# JETSON.net
KiCad netlist of a schematic drawn in Altium Designer
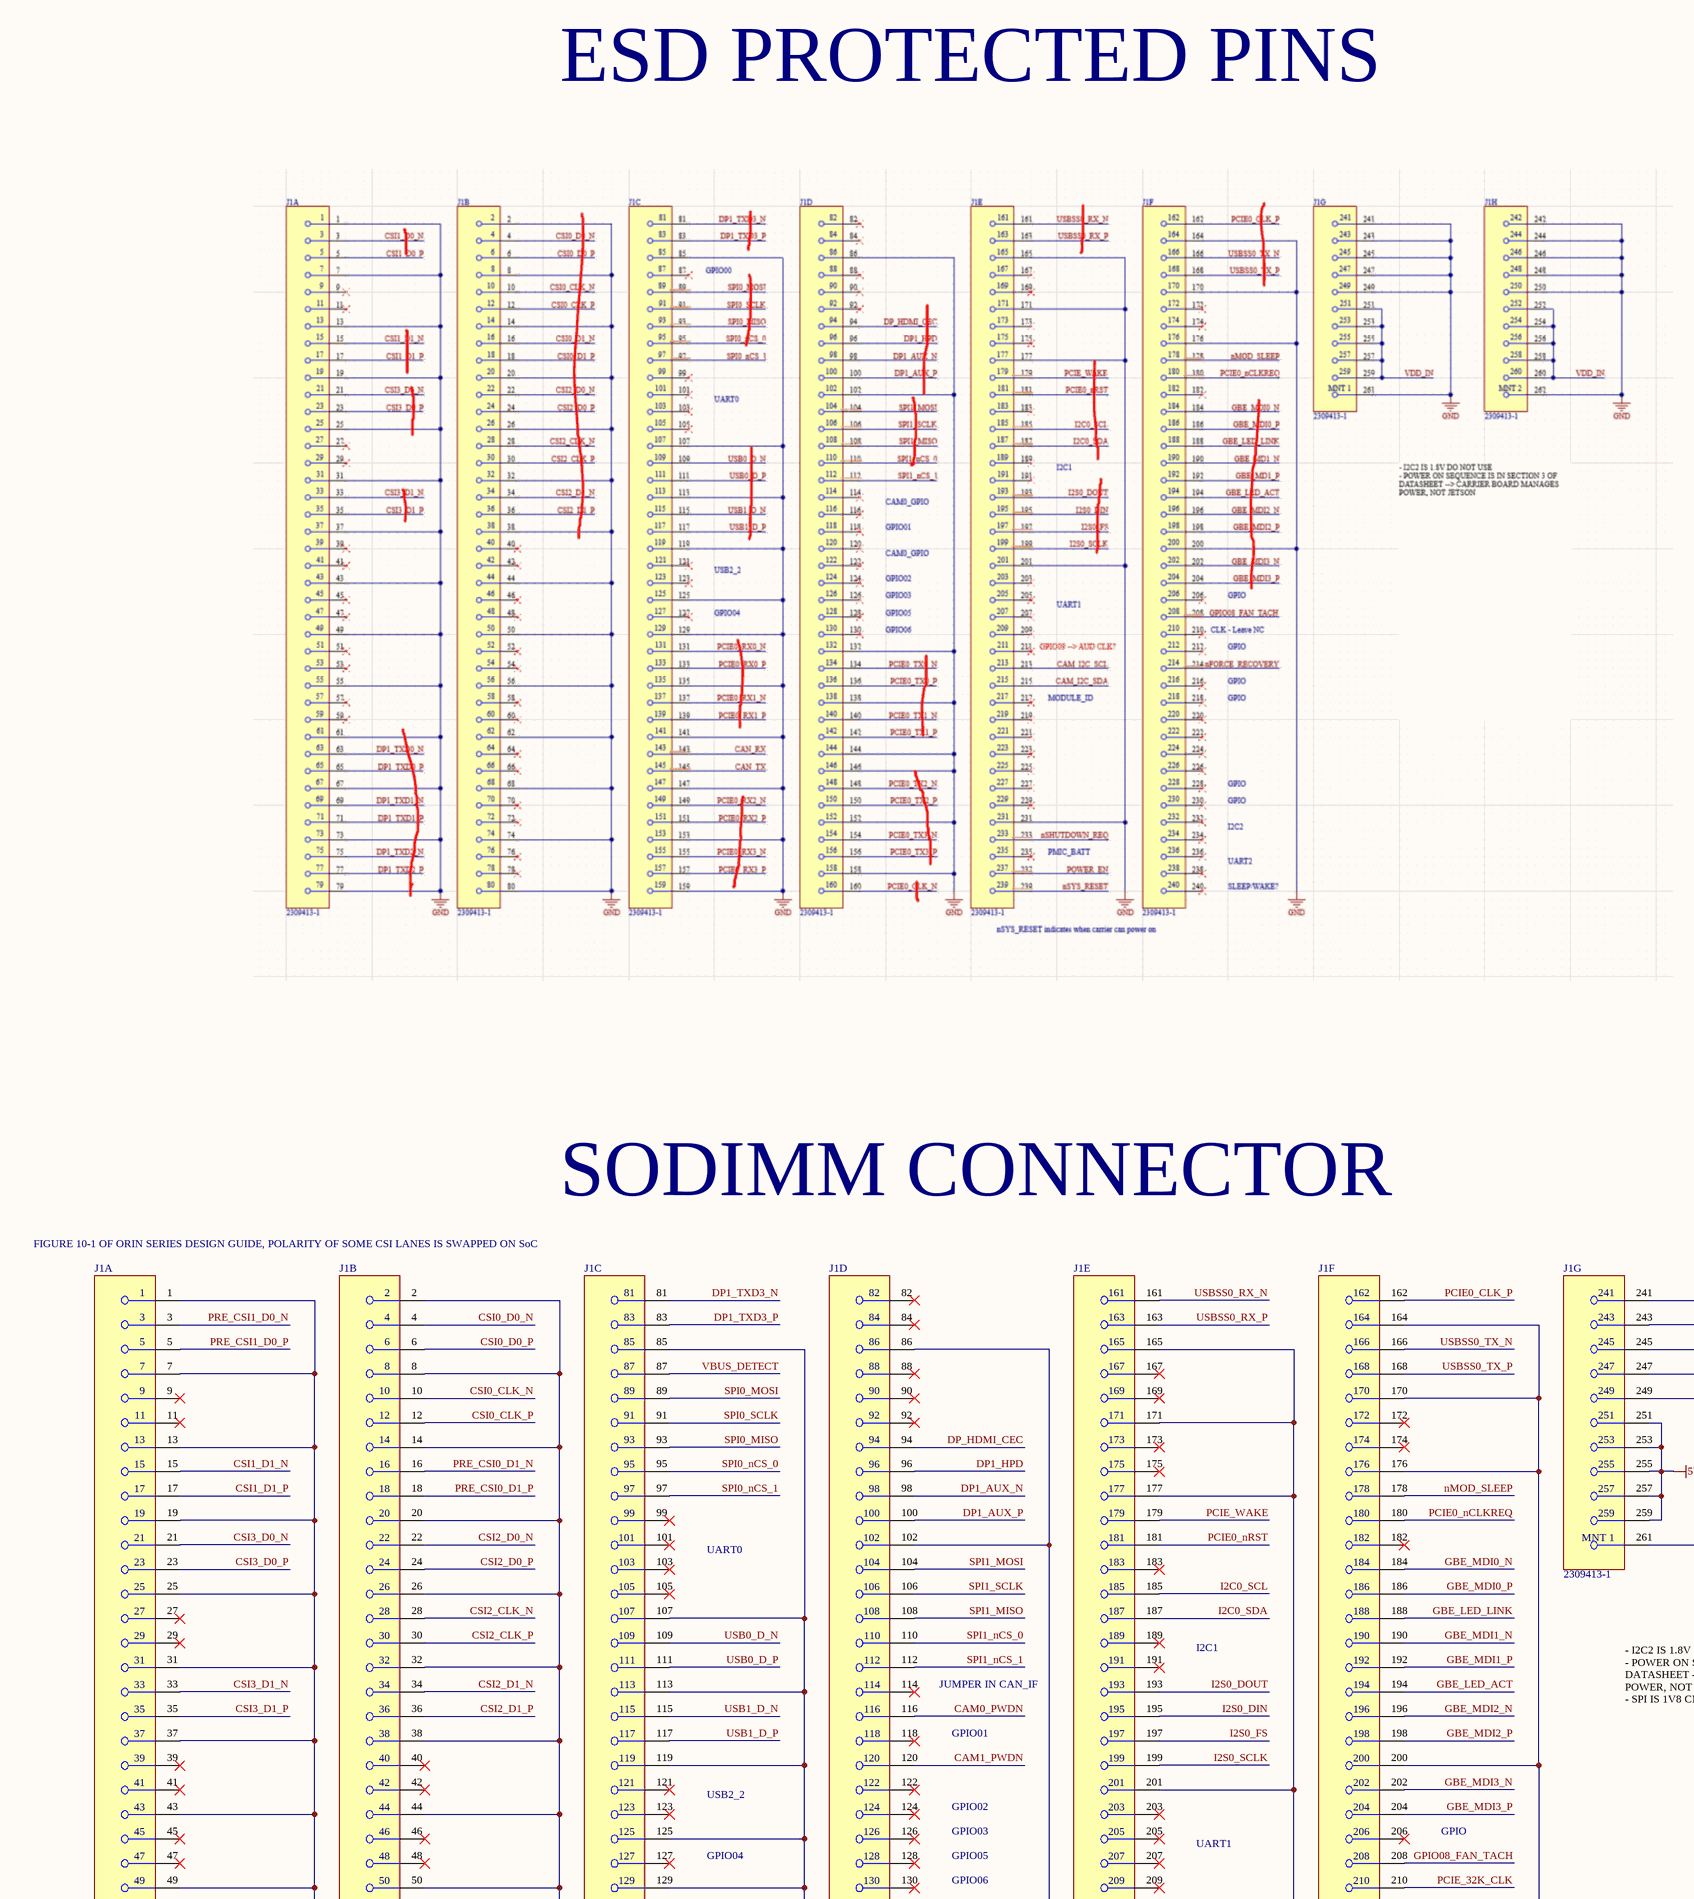
[diagram p0: JETSON.SchDoc, top left]
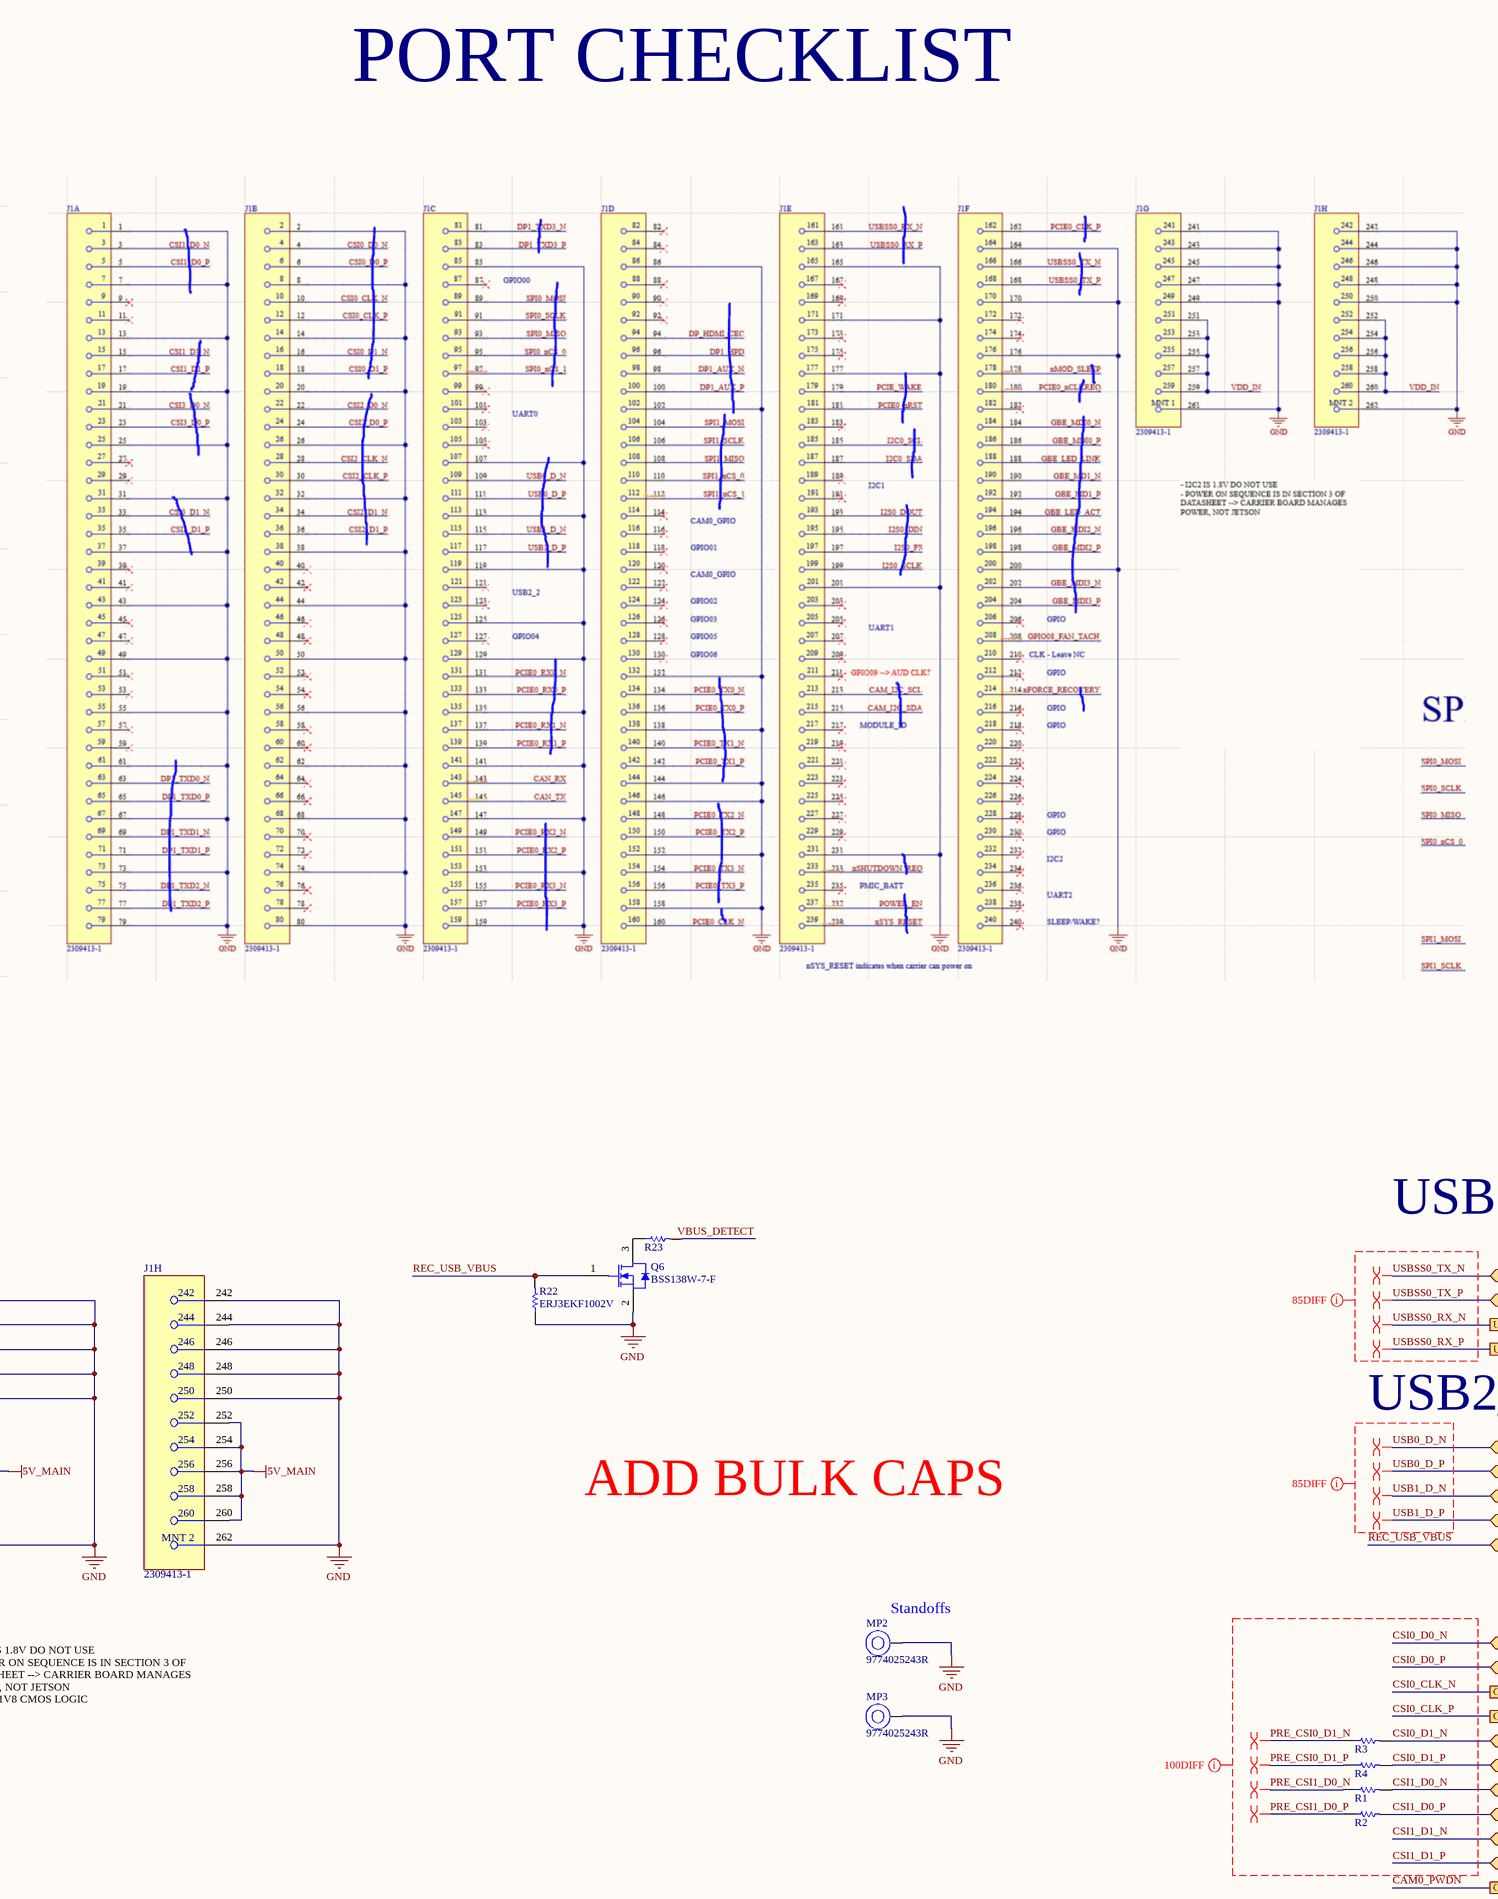
[diagram p1: JETSON.SchDoc, top middle]
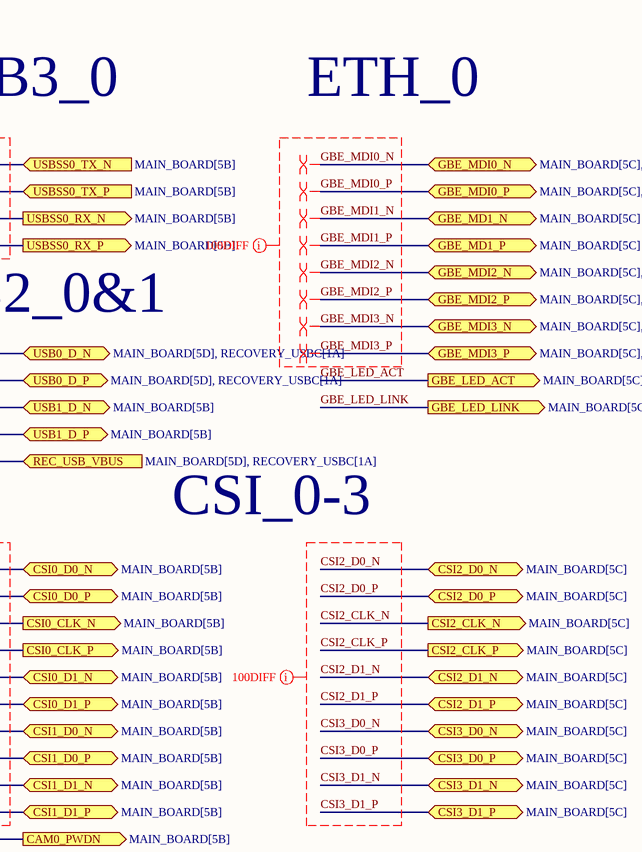
[diagram p2: JETSON.SchDoc, top right]
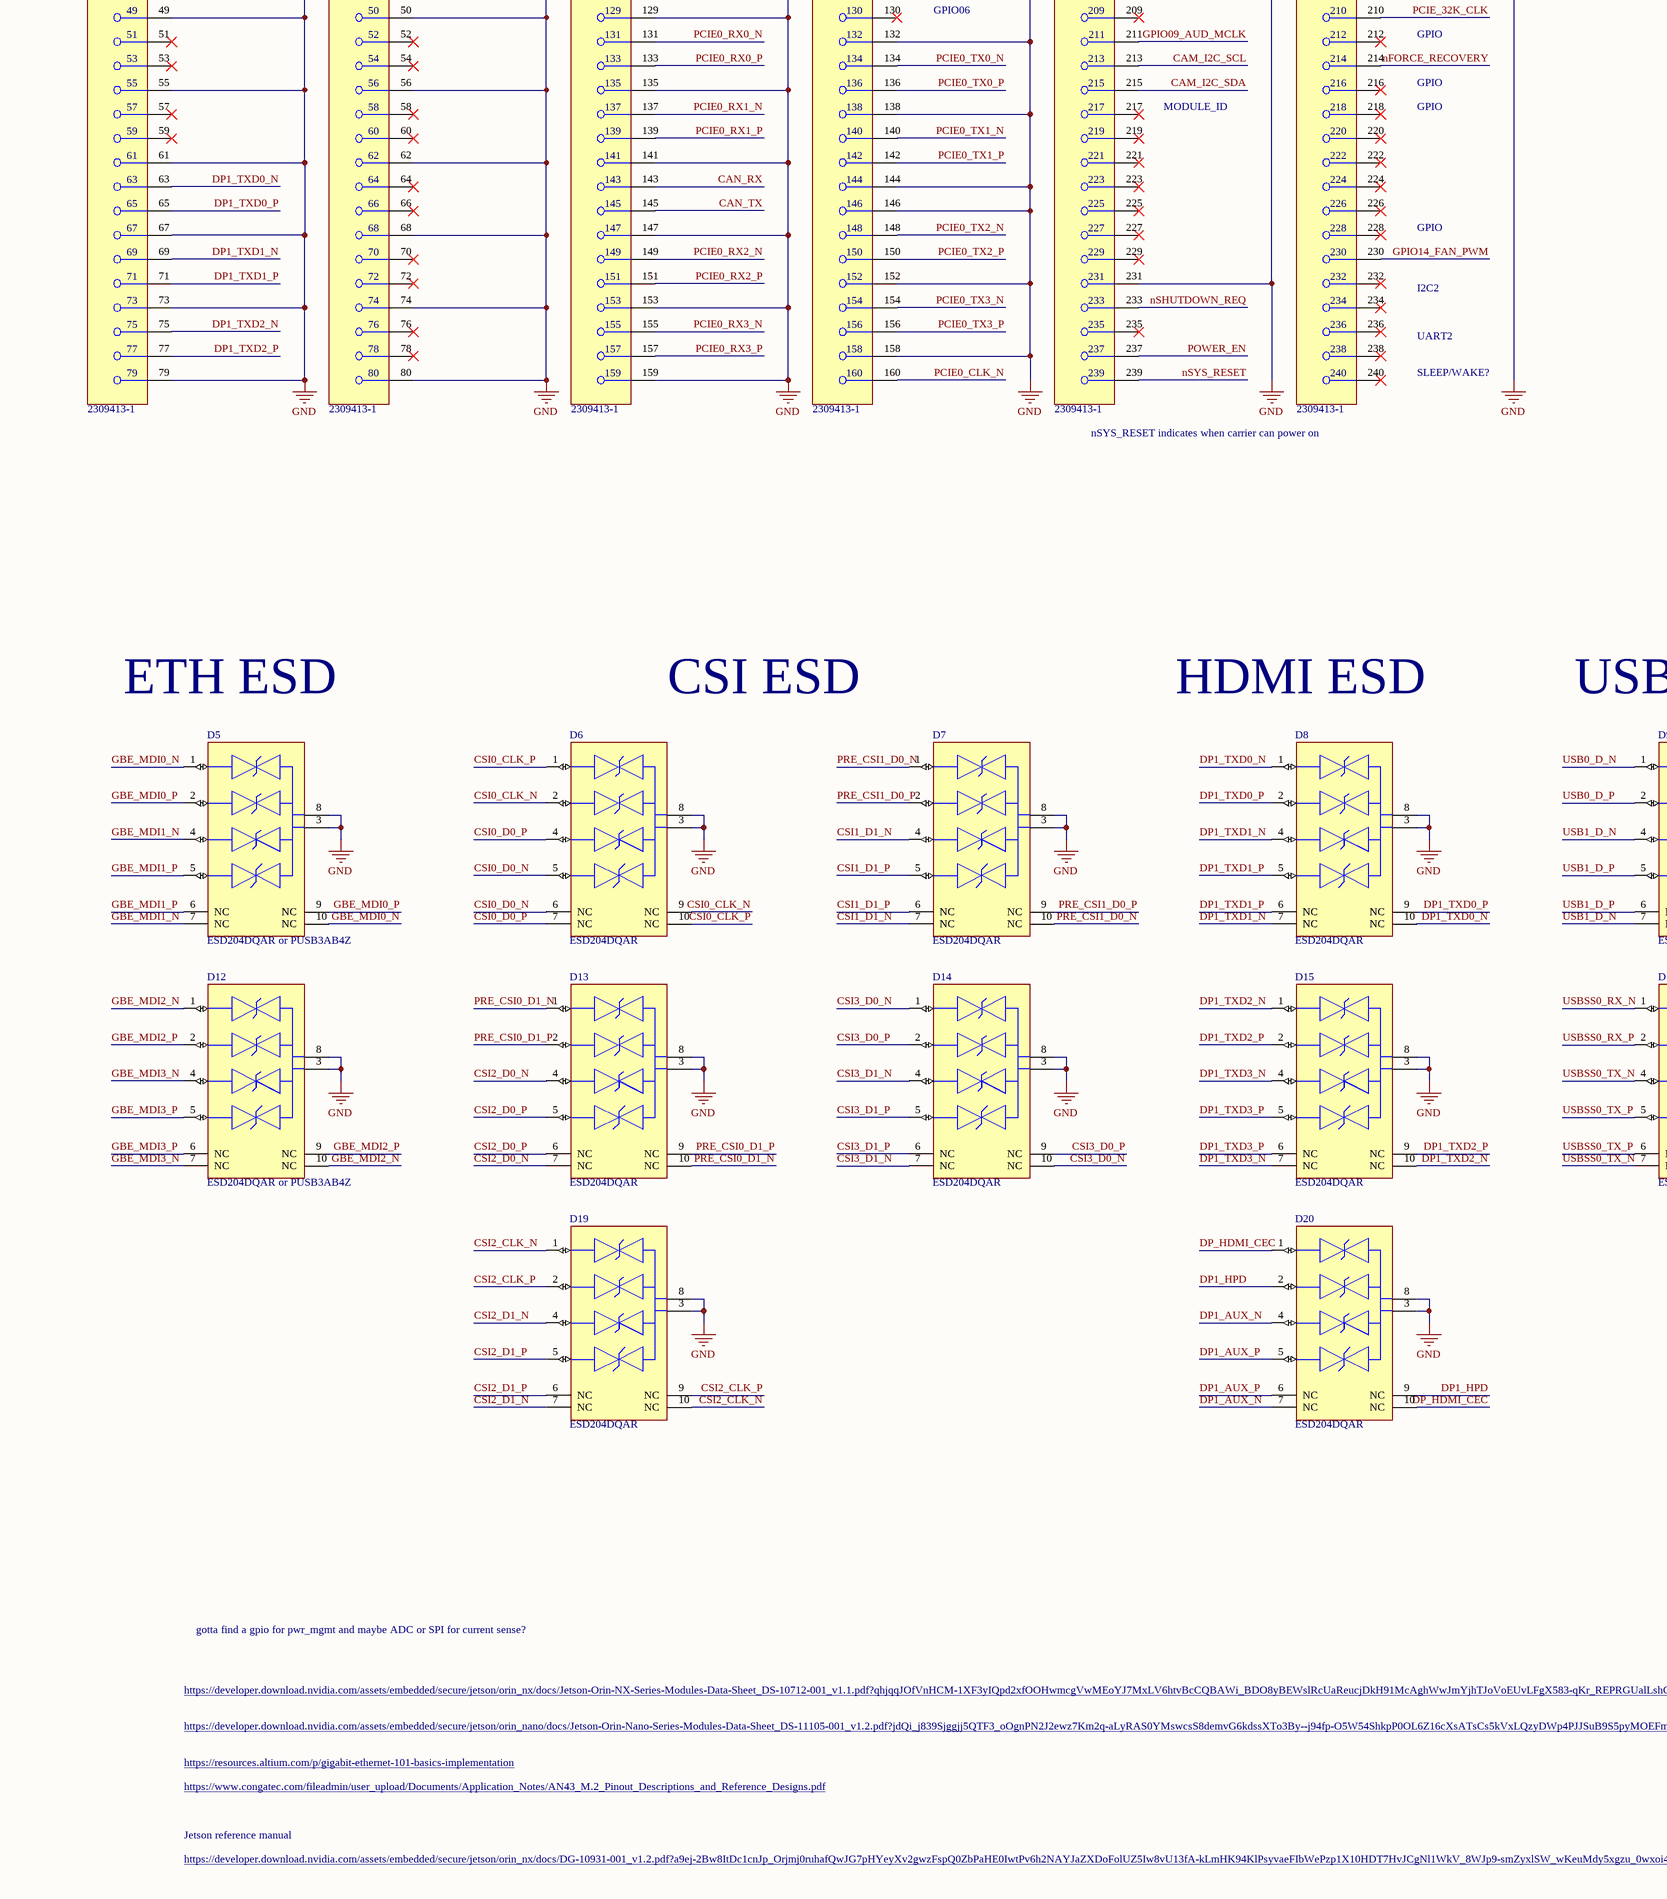
[diagram p3: JETSON.SchDoc, bottom left]
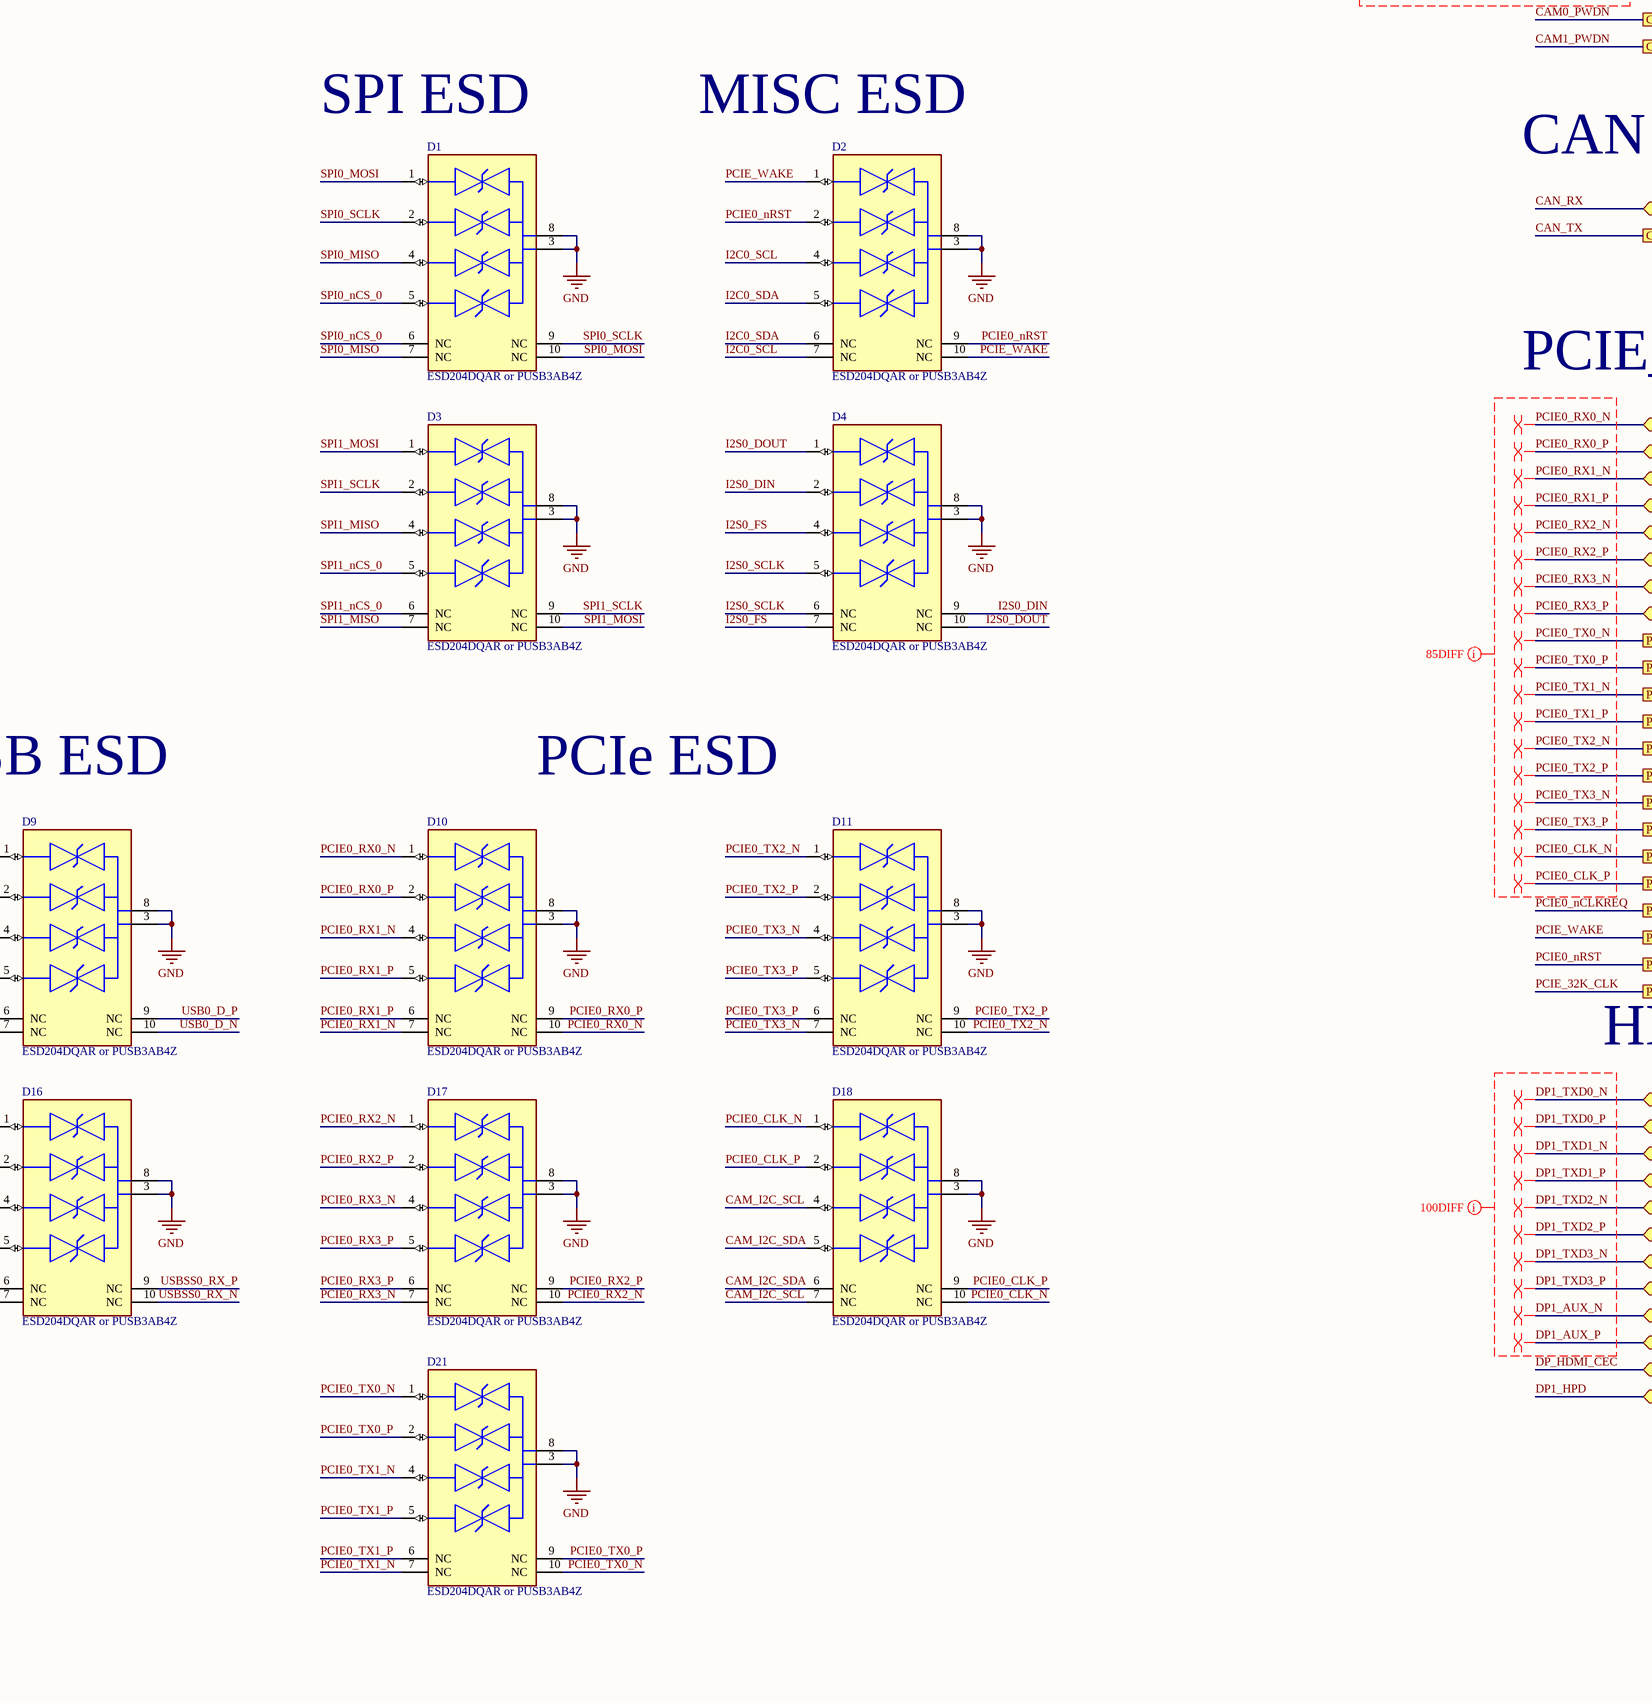
[diagram p4: JETSON.SchDoc, bottom middle]
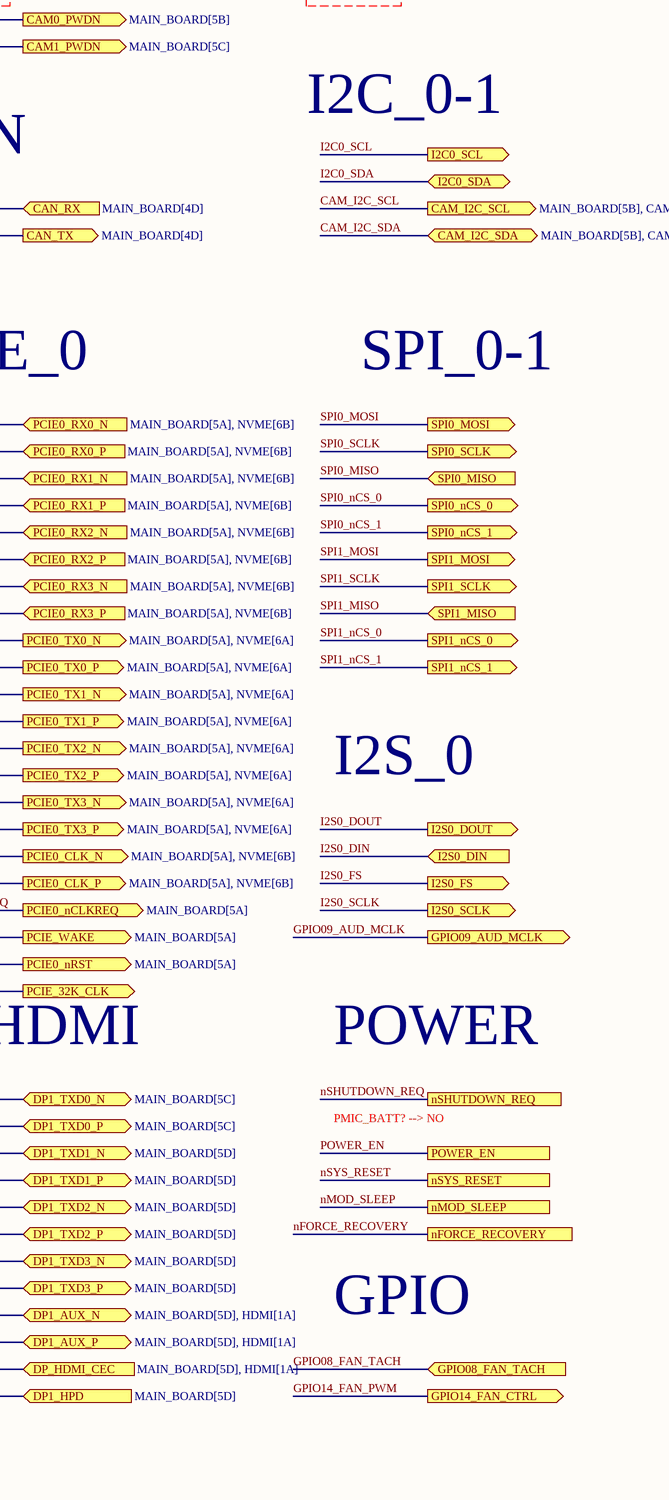
[diagram p5: JETSON.SchDoc, bottom right]

(export (version "E")
  (design (tool "Eeschema 10.0.6"))
  (components
    (comp (ref "D1")
      (value "ESD204DQAR or PUSB3AB4Z")
      (footprint "FP-DQA0010A-MFG")
      (description "4-CHANNEL LOW-CAPACITANCE SURGE")
      (fields
        (field (name "MANUFACTURER") "Texas Instruments")
        (field (name "OCTOPART") "https://octopart.com/esd204dqar-texas+instruments-89917476")
      )
      (libsource (lib "Altium Content Vault") (part "1465e58c1818c7767b55926832f0bf5"))
    )
    (comp (ref "D2")
      (value "ESD204DQAR or PUSB3AB4Z")
      (footprint "FP-DQA0010A-MFG")
      (description "4-CHANNEL LOW-CAPACITANCE SURGE")
      (fields
        (field (name "MANUFACTURER") "Texas Instruments")
        (field (name "OCTOPART") "https://octopart.com/esd204dqar-texas+instruments-89917476")
      )
      (libsource (lib "Altium Content Vault") (part "1465e58c1818c7767b55926832f0bf5"))
    )
    (comp (ref "D3")
      (value "ESD204DQAR or PUSB3AB4Z")
      (footprint "FP-DQA0010A-MFG")
      (description "4-CHANNEL LOW-CAPACITANCE SURGE")
      (fields
        (field (name "MANUFACTURER") "Texas Instruments")
        (field (name "OCTOPART") "https://octopart.com/esd204dqar-texas+instruments-89917476")
      )
      (libsource (lib "Altium Content Vault") (part "1465e58c1818c7767b55926832f0bf5"))
    )
    (comp (ref "D4")
      (value "ESD204DQAR or PUSB3AB4Z")
      (footprint "FP-DQA0010A-MFG")
      (description "4-CHANNEL LOW-CAPACITANCE SURGE")
      (fields
        (field (name "MANUFACTURER") "Texas Instruments")
        (field (name "OCTOPART") "https://octopart.com/esd204dqar-texas+instruments-89917476")
      )
      (libsource (lib "Altium Content Vault") (part "1465e58c1818c7767b55926832f0bf5"))
    )
    (comp (ref "D5")
      (value "ESD204DQAR or PUSB3AB4Z")
      (footprint "FP-DQA0010A-MFG")
      (description "4-CHANNEL LOW-CAPACITANCE SURGE")
      (fields
        (field (name "MANUFACTURER") "Texas Instruments")
        (field (name "OCTOPART") "https://octopart.com/esd204dqar-texas+instruments-89917476")
      )
      (libsource (lib "Altium Content Vault") (part "1465e58c1818c7767b55926832f0bf5"))
    )
    (comp (ref "D6")
      (value "ESD204DQAR")
      (footprint "FP-DQA0010A-MFG")
      (description "4-CHANNEL LOW-CAPACITANCE SURGE")
      (fields
        (field (name "MANUFACTURER") "Texas Instruments")
        (field (name "OCTOPART") "https://octopart.com/esd204dqar-texas+instruments-89917476")
      )
      (libsource (lib "Altium Content Vault") (part "1465e58c1818c7767b55926832f0bf5"))
    )
    (comp (ref "D7")
      (value "ESD204DQAR")
      (footprint "FP-DQA0010A-MFG")
      (description "4-CHANNEL LOW-CAPACITANCE SURGE")
      (fields
        (field (name "MANUFACTURER") "Texas Instruments")
        (field (name "OCTOPART") "https://octopart.com/esd204dqar-texas+instruments-89917476")
      )
      (libsource (lib "Altium Content Vault") (part "1465e58c1818c7767b55926832f0bf5"))
    )
    (comp (ref "D8")
      (value "ESD204DQAR")
      (footprint "FP-DQA0010A-MFG")
      (description "4-CHANNEL LOW-CAPACITANCE SURGE")
      (fields
        (field (name "MANUFACTURER") "Texas Instruments")
        (field (name "OCTOPART") "https://octopart.com/esd204dqar-texas+instruments-89917476")
      )
      (libsource (lib "Altium Content Vault") (part "1465e58c1818c7767b55926832f0bf5"))
    )
    (comp (ref "D9")
      (value "ESD204DQAR or PUSB3AB4Z")
      (footprint "FP-DQA0010A-MFG")
      (description "4-CHANNEL LOW-CAPACITANCE SURGE")
      (fields
        (field (name "MANUFACTURER") "Texas Instruments")
        (field (name "OCTOPART") "https://octopart.com/esd204dqar-texas+instruments-89917476")
      )
      (libsource (lib "Altium Content Vault") (part "1465e58c1818c7767b55926832f0bf5"))
    )
    (comp (ref "D10")
      (value "ESD204DQAR or PUSB3AB4Z")
      (footprint "FP-DQA0010A-MFG")
      (description "4-CHANNEL LOW-CAPACITANCE SURGE")
      (fields
        (field (name "MANUFACTURER") "Texas Instruments")
        (field (name "OCTOPART") "https://octopart.com/esd204dqar-texas+instruments-89917476")
      )
      (libsource (lib "Altium Content Vault") (part "1465e58c1818c7767b55926832f0bf5"))
    )
    (comp (ref "D11")
      (value "ESD204DQAR or PUSB3AB4Z")
      (footprint "FP-DQA0010A-MFG")
      (description "4-CHANNEL LOW-CAPACITANCE SURGE")
      (fields
        (field (name "MANUFACTURER") "Texas Instruments")
        (field (name "OCTOPART") "https://octopart.com/esd204dqar-texas+instruments-89917476")
      )
      (libsource (lib "Altium Content Vault") (part "1465e58c1818c7767b55926832f0bf5"))
    )
    (comp (ref "D12")
      (value "ESD204DQAR or PUSB3AB4Z")
      (footprint "FP-DQA0010A-MFG")
      (description "4-CHANNEL LOW-CAPACITANCE SURGE")
      (fields
        (field (name "MANUFACTURER") "Texas Instruments")
        (field (name "OCTOPART") "https://octopart.com/esd204dqar-texas+instruments-89917476")
      )
      (libsource (lib "Altium Content Vault") (part "1465e58c1818c7767b55926832f0bf5"))
    )
    (comp (ref "D13")
      (value "ESD204DQAR")
      (footprint "FP-DQA0010A-MFG")
      (description "4-CHANNEL LOW-CAPACITANCE SURGE")
      (fields
        (field (name "MANUFACTURER") "Texas Instruments")
        (field (name "OCTOPART") "https://octopart.com/esd204dqar-texas+instruments-89917476")
      )
      (libsource (lib "Altium Content Vault") (part "1465e58c1818c7767b55926832f0bf5"))
    )
    (comp (ref "D14")
      (value "ESD204DQAR")
      (footprint "FP-DQA0010A-MFG")
      (description "4-CHANNEL LOW-CAPACITANCE SURGE")
      (fields
        (field (name "MANUFACTURER") "Texas Instruments")
        (field (name "OCTOPART") "https://octopart.com/esd204dqar-texas+instruments-89917476")
      )
      (libsource (lib "Altium Content Vault") (part "1465e58c1818c7767b55926832f0bf5"))
    )
    (comp (ref "D15")
      (value "ESD204DQAR")
      (footprint "FP-DQA0010A-MFG")
      (description "4-CHANNEL LOW-CAPACITANCE SURGE")
      (fields
        (field (name "MANUFACTURER") "Texas Instruments")
        (field (name "OCTOPART") "https://octopart.com/esd204dqar-texas+instruments-89917476")
      )
      (libsource (lib "Altium Content Vault") (part "1465e58c1818c7767b55926832f0bf5"))
    )
    (comp (ref "D16")
      (value "ESD204DQAR or PUSB3AB4Z")
      (footprint "FP-DQA0010A-MFG")
      (description "4-CHANNEL LOW-CAPACITANCE SURGE")
      (fields
        (field (name "MANUFACTURER") "Texas Instruments")
        (field (name "OCTOPART") "https://octopart.com/esd204dqar-texas+instruments-89917476")
      )
      (libsource (lib "Altium Content Vault") (part "1465e58c1818c7767b55926832f0bf5"))
    )
    (comp (ref "D17")
      (value "ESD204DQAR or PUSB3AB4Z")
      (footprint "FP-DQA0010A-MFG")
      (description "4-CHANNEL LOW-CAPACITANCE SURGE")
      (fields
        (field (name "MANUFACTURER") "Texas Instruments")
        (field (name "OCTOPART") "https://octopart.com/esd204dqar-texas+instruments-89917476")
      )
      (libsource (lib "Altium Content Vault") (part "1465e58c1818c7767b55926832f0bf5"))
    )
    (comp (ref "D18")
      (value "ESD204DQAR or PUSB3AB4Z")
      (footprint "FP-DQA0010A-MFG")
      (description "4-CHANNEL LOW-CAPACITANCE SURGE")
      (fields
        (field (name "MANUFACTURER") "Texas Instruments")
        (field (name "OCTOPART") "https://octopart.com/esd204dqar-texas+instruments-89917476")
      )
      (libsource (lib "Altium Content Vault") (part "1465e58c1818c7767b55926832f0bf5"))
    )
    (comp (ref "D19")
      (value "ESD204DQAR")
      (footprint "FP-DQA0010A-MFG")
      (description "4-CHANNEL LOW-CAPACITANCE SURGE")
      (fields
        (field (name "MANUFACTURER") "Texas Instruments")
        (field (name "OCTOPART") "https://octopart.com/esd204dqar-texas+instruments-89917476")
      )
      (libsource (lib "Altium Content Vault") (part "1465e58c1818c7767b55926832f0bf5"))
    )
    (comp (ref "D20")
      (value "ESD204DQAR")
      (footprint "FP-DQA0010A-MFG")
      (description "4-CHANNEL LOW-CAPACITANCE SURGE")
      (fields
        (field (name "MANUFACTURER") "Texas Instruments")
        (field (name "OCTOPART") "https://octopart.com/esd204dqar-texas+instruments-89917476")
      )
      (libsource (lib "Altium Content Vault") (part "1465e58c1818c7767b55926832f0bf5"))
    )
    (comp (ref "D21")
      (value "ESD204DQAR or PUSB3AB4Z")
      (footprint "FP-DQA0010A-MFG")
      (description "4-CHANNEL LOW-CAPACITANCE SURGE")
      (fields
        (field (name "MANUFACTURER") "Texas Instruments")
        (field (name "OCTOPART") "https://octopart.com/esd204dqar-texas+instruments-89917476")
      )
      (libsource (lib "Altium Content Vault") (part "1465e58c1818c7767b55926832f0bf5"))
    )
    (comp (ref "J1")
      (value "2309413-1")
      (footprint "FP-2309413-1-MFG")
      (description "DDR4 SODIMM 260P 9.2H STD")
      (fields
        (field (name "OCTOPART") "https://octopart.com/2309413-1-te+connectivity-84799194")
        (field (name "MANUFACTURER") "TE Connectivity")
      )
      (libsource (lib "Altium Content Vault") (part "4d1075b24ee2591bdcd47d674b3d2aa"))
    )
    (comp (ref "MP2")
      (value "9774025243R")
      (footprint "9774025243")
      (description "9774025243R Spacer Material: Steel, Tin-Plated Mounting: SMT Series: WA-SMST Thread D: M2")
      (libsource (lib "Altium Content Vault") (part "Spacer"))
    )
    (comp (ref "MP3")
      (value "9774025243R")
      (footprint "9774025243")
      (description "9774025243R Spacer Material: Steel, Tin-Plated Mounting: SMT Series: WA-SMST Thread D: M2")
      (libsource (lib "Altium Content Vault") (part "Spacer"))
    )
    (comp (ref "Q6")
      (value "BSS138W-7-F")
      (footprint "DIOD-SOT323-3_V")
      (fields (field (name "MANUFACTURER") "DiodesIncorporated"))
      (libsource (lib "Altium Content Vault") (part "NEMOS-GSD-3"))
    )
    (comp (ref "R1")
      (value "0402 JUMPER 0 OHM")
      (footprint "RESC1005X40X25NL05T05")
      (description "READ THE NAME")
      (libsource (lib "uORocketry Hardware") (part "RES"))
    )
    (comp (ref "R2")
      (value "0402 JUMPER 0 OHM")
      (footprint "RESC1005X40X25NL05T05")
      (description "READ THE NAME")
      (libsource (lib "uORocketry Hardware") (part "RES"))
    )
    (comp (ref "R3")
      (value "0402 JUMPER 0 OHM")
      (footprint "RESC1005X40X25NL05T05")
      (description "READ THE NAME")
      (libsource (lib "uORocketry Hardware") (part "RES"))
    )
    (comp (ref "R4")
      (value "0402 JUMPER 0 OHM")
      (footprint "RESC1005X40X25NL05T05")
      (description "READ THE NAME")
      (libsource (lib "uORocketry Hardware") (part "RES"))
    )
    (comp (ref "R22")
      (value "ERJ3EKF1002V")
      (footprint "RESC1609X55X30LL15T15")
      (description "Chip Resistor, 10 KOhm, +/- 1%, 0.1 W, -55 to 155 degC, 0603 (1608 Metric), RoHS, Tape and Reel")
      (fields (field (name "TOLERANCE") "1%") (field (name "MANUFACTURER") "Panasonic"))
      (libsource (lib "Altium Content Vault") (part "RES-2"))
    )
    (comp (ref "R23")
      (value "0402 JUMPER 0 OHM")
      (footprint "RESC1005X40X25NL05T05")
      (description "READ THE NAME")
      (libsource (lib "uORocketry Hardware") (part "RES"))
    )
  )
  (nets
    (net (code "1") (name "/CAM0_PWDN") (class "Default")
      (node (ref "J1") (pin "116") (pinfunction "116_116") (pintype "passive"))
    )
    (net (code "2") (name "/CAM1_PWDN") (class "Default")
      (node (ref "J1") (pin "120") (pinfunction "120_120") (pintype "passive"))
    )
    (net (code "3") (name "/CAM_I2C_SCL") (class "Default")
      (node (ref "D18") (pin "4") (pinfunction "IO3_4") (pintype "bidirectional"))
      (node (ref "D18") (pin "7") (pinfunction "NC_7") (pintype "passive"))
      (node (ref "J1") (pin "213") (pinfunction "213_213") (pintype "passive"))
    )
    (net (code "4") (name "/CAM_I2C_SDA") (class "Default")
      (node (ref "D18") (pin "5") (pinfunction "IO4_5") (pintype "bidirectional"))
      (node (ref "D18") (pin "6") (pinfunction "NC_6") (pintype "passive"))
      (node (ref "J1") (pin "215") (pinfunction "215_215") (pintype "passive"))
    )
    (net (code "5") (name "/CAN_RX") (class "Default")
      (node (ref "J1") (pin "143") (pinfunction "143_143") (pintype "passive"))
    )
    (net (code "6") (name "/CAN_TX") (class "Default")
      (node (ref "J1") (pin "145") (pinfunction "145_145") (pintype "passive"))
    )
    (net (code "7") (name "/CSI0_CLK_N") (class "Default")
      (node (ref "D6") (pin "2") (pinfunction "IO2_2") (pintype "bidirectional"))
      (node (ref "D6") (pin "9") (pinfunction "NC_9") (pintype "passive"))
      (node (ref "J1") (pin "10") (pinfunction "10_10") (pintype "passive"))
    )
    (net (code "8") (name "/CSI0_CLK_P") (class "Default")
      (node (ref "D6") (pin "1") (pinfunction "IO1_1") (pintype "bidirectional"))
      (node (ref "D6") (pin "10") (pinfunction "NC_10") (pintype "passive"))
      (node (ref "J1") (pin "12") (pinfunction "12_12") (pintype "passive"))
    )
    (net (code "9") (name "/CSI0_D0_N") (class "Default")
      (node (ref "D6") (pin "5") (pinfunction "IO4_5") (pintype "bidirectional"))
      (node (ref "D6") (pin "6") (pinfunction "NC_6") (pintype "passive"))
      (node (ref "J1") (pin "4") (pinfunction "4_4") (pintype "passive"))
    )
    (net (code "10") (name "/CSI0_D0_P") (class "Default")
      (node (ref "D6") (pin "4") (pinfunction "IO3_4") (pintype "bidirectional"))
      (node (ref "D6") (pin "7") (pinfunction "NC_7") (pintype "passive"))
      (node (ref "J1") (pin "6") (pinfunction "6_6") (pintype "passive"))
    )
    (net (code "11") (name "/CSI0_D1_N") (class "Default")
      (node (ref "R3") (pin "2") (pinfunction "2_2") (pintype "passive"))
    )
    (net (code "12") (name "/CSI0_D1_P") (class "Default")
      (node (ref "R4") (pin "2") (pinfunction "2_2") (pintype "passive"))
    )
    (net (code "13") (name "/CSI1_D0_N") (class "Default")
      (node (ref "R1") (pin "2") (pinfunction "2_2") (pintype "passive"))
    )
    (net (code "14") (name "/CSI1_D0_P") (class "Default")
      (node (ref "R2") (pin "2") (pinfunction "2_2") (pintype "passive"))
    )
    (net (code "15") (name "/CSI1_D1_N") (class "Default")
      (node (ref "D7") (pin "4") (pinfunction "IO3_4") (pintype "bidirectional"))
      (node (ref "D7") (pin "7") (pinfunction "NC_7") (pintype "passive"))
      (node (ref "J1") (pin "15") (pinfunction "15_15") (pintype "passive"))
    )
    (net (code "16") (name "/CSI1_D1_P") (class "Default")
      (node (ref "D7") (pin "5") (pinfunction "IO4_5") (pintype "bidirectional"))
      (node (ref "D7") (pin "6") (pinfunction "NC_6") (pintype "passive"))
      (node (ref "J1") (pin "17") (pinfunction "17_17") (pintype "passive"))
    )
    (net (code "17") (name "/CSI2_CLK_N") (class "Default")
      (node (ref "D19") (pin "1") (pinfunction "IO1_1") (pintype "bidirectional"))
      (node (ref "D19") (pin "10") (pinfunction "NC_10") (pintype "passive"))
      (node (ref "J1") (pin "28") (pinfunction "28_28") (pintype "passive"))
    )
    (net (code "18") (name "/CSI2_CLK_P") (class "Default")
      (node (ref "D19") (pin "2") (pinfunction "IO2_2") (pintype "bidirectional"))
      (node (ref "D19") (pin "9") (pinfunction "NC_9") (pintype "passive"))
      (node (ref "J1") (pin "30") (pinfunction "30_30") (pintype "passive"))
    )
    (net (code "19") (name "/CSI2_D0_N") (class "Default")
      (node (ref "D13") (pin "4") (pinfunction "IO3_4") (pintype "bidirectional"))
      (node (ref "D13") (pin "7") (pinfunction "NC_7") (pintype "passive"))
      (node (ref "J1") (pin "22") (pinfunction "22_22") (pintype "passive"))
    )
    (net (code "20") (name "/CSI2_D0_P") (class "Default")
      (node (ref "D13") (pin "5") (pinfunction "IO4_5") (pintype "bidirectional"))
      (node (ref "D13") (pin "6") (pinfunction "NC_6") (pintype "passive"))
      (node (ref "J1") (pin "24") (pinfunction "24_24") (pintype "passive"))
    )
    (net (code "21") (name "/CSI2_D1_N") (class "Default")
      (node (ref "D19") (pin "4") (pinfunction "IO3_4") (pintype "bidirectional"))
      (node (ref "D19") (pin "7") (pinfunction "NC_7") (pintype "passive"))
      (node (ref "J1") (pin "34") (pinfunction "34_34") (pintype "passive"))
    )
    (net (code "22") (name "/CSI2_D1_P") (class "Default")
      (node (ref "D19") (pin "5") (pinfunction "IO4_5") (pintype "bidirectional"))
      (node (ref "D19") (pin "6") (pinfunction "NC_6") (pintype "passive"))
      (node (ref "J1") (pin "36") (pinfunction "36_36") (pintype "passive"))
    )
    (net (code "23") (name "/CSI3_D0_N") (class "Default")
      (node (ref "D14") (pin "1") (pinfunction "IO1_1") (pintype "bidirectional"))
      (node (ref "D14") (pin "10") (pinfunction "NC_10") (pintype "passive"))
      (node (ref "J1") (pin "21") (pinfunction "21_21") (pintype "passive"))
    )
    (net (code "24") (name "/CSI3_D0_P") (class "Default")
      (node (ref "D14") (pin "2") (pinfunction "IO2_2") (pintype "bidirectional"))
      (node (ref "D14") (pin "9") (pinfunction "NC_9") (pintype "passive"))
      (node (ref "J1") (pin "23") (pinfunction "23_23") (pintype "passive"))
    )
    (net (code "25") (name "/CSI3_D1_N") (class "Default")
      (node (ref "D14") (pin "4") (pinfunction "IO3_4") (pintype "bidirectional"))
      (node (ref "D14") (pin "7") (pinfunction "NC_7") (pintype "passive"))
      (node (ref "J1") (pin "33") (pinfunction "33_33") (pintype "passive"))
    )
    (net (code "26") (name "/CSI3_D1_P") (class "Default")
      (node (ref "D14") (pin "5") (pinfunction "IO4_5") (pintype "bidirectional"))
      (node (ref "D14") (pin "6") (pinfunction "NC_6") (pintype "passive"))
      (node (ref "J1") (pin "35") (pinfunction "35_35") (pintype "passive"))
    )
    (net (code "27") (name "/DP1_AUX_N") (class "Default")
      (node (ref "D20") (pin "4") (pinfunction "IO3_4") (pintype "bidirectional"))
      (node (ref "D20") (pin "7") (pinfunction "NC_7") (pintype "passive"))
      (node (ref "J1") (pin "98") (pinfunction "98_98") (pintype "passive"))
    )
    (net (code "28") (name "/DP1_AUX_P") (class "Default")
      (node (ref "D20") (pin "5") (pinfunction "IO4_5") (pintype "bidirectional"))
      (node (ref "D20") (pin "6") (pinfunction "NC_6") (pintype "passive"))
      (node (ref "J1") (pin "100") (pinfunction "100_100") (pintype "passive"))
    )
    (net (code "29") (name "/DP1_HPD") (class "Default")
      (node (ref "D20") (pin "2") (pinfunction "IO2_2") (pintype "bidirectional"))
      (node (ref "D20") (pin "9") (pinfunction "NC_9") (pintype "passive"))
      (node (ref "J1") (pin "96") (pinfunction "96_96") (pintype "passive"))
    )
    (net (code "30") (name "/DP1_TXD0_N") (class "Default")
      (node (ref "D8") (pin "1") (pinfunction "IO1_1") (pintype "bidirectional"))
      (node (ref "D8") (pin "10") (pinfunction "NC_10") (pintype "passive"))
      (node (ref "J1") (pin "63") (pinfunction "63_63") (pintype "passive"))
    )
    (net (code "31") (name "/DP1_TXD0_P") (class "Default")
      (node (ref "D8") (pin "2") (pinfunction "IO2_2") (pintype "bidirectional"))
      (node (ref "D8") (pin "9") (pinfunction "NC_9") (pintype "passive"))
      (node (ref "J1") (pin "65") (pinfunction "65_65") (pintype "passive"))
    )
    (net (code "32") (name "/DP1_TXD1_N") (class "Default")
      (node (ref "D8") (pin "4") (pinfunction "IO3_4") (pintype "bidirectional"))
      (node (ref "D8") (pin "7") (pinfunction "NC_7") (pintype "passive"))
      (node (ref "J1") (pin "69") (pinfunction "69_69") (pintype "passive"))
    )
    (net (code "33") (name "/DP1_TXD1_P") (class "Default")
      (node (ref "D8") (pin "5") (pinfunction "IO4_5") (pintype "bidirectional"))
      (node (ref "D8") (pin "6") (pinfunction "NC_6") (pintype "passive"))
      (node (ref "J1") (pin "71") (pinfunction "71_71") (pintype "passive"))
    )
    (net (code "34") (name "/DP1_TXD2_N") (class "Default")
      (node (ref "D15") (pin "1") (pinfunction "IO1_1") (pintype "bidirectional"))
      (node (ref "D15") (pin "10") (pinfunction "NC_10") (pintype "passive"))
      (node (ref "J1") (pin "75") (pinfunction "75_75") (pintype "passive"))
    )
    (net (code "35") (name "/DP1_TXD2_P") (class "Default")
      (node (ref "D15") (pin "2") (pinfunction "IO2_2") (pintype "bidirectional"))
      (node (ref "D15") (pin "9") (pinfunction "NC_9") (pintype "passive"))
      (node (ref "J1") (pin "77") (pinfunction "77_77") (pintype "passive"))
    )
    (net (code "36") (name "/DP1_TXD3_N") (class "Default")
      (node (ref "D15") (pin "4") (pinfunction "IO3_4") (pintype "bidirectional"))
      (node (ref "D15") (pin "7") (pinfunction "NC_7") (pintype "passive"))
      (node (ref "J1") (pin "81") (pinfunction "81_81") (pintype "passive"))
    )
    (net (code "37") (name "/DP1_TXD3_P") (class "Default")
      (node (ref "D15") (pin "5") (pinfunction "IO4_5") (pintype "bidirectional"))
      (node (ref "D15") (pin "6") (pinfunction "NC_6") (pintype "passive"))
      (node (ref "J1") (pin "83") (pinfunction "83_83") (pintype "passive"))
    )
    (net (code "38") (name "/DP_HDMI_CEC") (class "Default")
      (node (ref "D20") (pin "1") (pinfunction "IO1_1") (pintype "bidirectional"))
      (node (ref "D20") (pin "10") (pinfunction "NC_10") (pintype "passive"))
      (node (ref "J1") (pin "94") (pinfunction "94_94") (pintype "passive"))
    )
    (net (code "39") (name "/GBE_LED_ACT") (class "Default")
      (node (ref "J1") (pin "194") (pinfunction "194_194") (pintype "passive"))
    )
    (net (code "40") (name "/GBE_LED_LINK") (class "Default")
      (node (ref "J1") (pin "188") (pinfunction "188_188") (pintype "passive"))
    )
    (net (code "41") (name "/GBE_MDI0_N") (class "Default")
      (node (ref "D5") (pin "1") (pinfunction "IO1_1") (pintype "bidirectional"))
      (node (ref "D5") (pin "10") (pinfunction "NC_10") (pintype "passive"))
      (node (ref "J1") (pin "184") (pinfunction "184_184") (pintype "passive"))
    )
    (net (code "42") (name "/GBE_MDI0_P") (class "Default")
      (node (ref "D5") (pin "2") (pinfunction "IO2_2") (pintype "bidirectional"))
      (node (ref "D5") (pin "9") (pinfunction "NC_9") (pintype "passive"))
      (node (ref "J1") (pin "186") (pinfunction "186_186") (pintype "passive"))
    )
    (net (code "43") (name "/GBE_MDI1_N") (class "Default")
      (node (ref "D5") (pin "4") (pinfunction "IO3_4") (pintype "bidirectional"))
      (node (ref "D5") (pin "7") (pinfunction "NC_7") (pintype "passive"))
      (node (ref "J1") (pin "190") (pinfunction "190_190") (pintype "passive"))
    )
    (net (code "44") (name "/GBE_MDI1_P") (class "Default")
      (node (ref "D5") (pin "5") (pinfunction "IO4_5") (pintype "bidirectional"))
      (node (ref "D5") (pin "6") (pinfunction "NC_6") (pintype "passive"))
      (node (ref "J1") (pin "192") (pinfunction "192_192") (pintype "passive"))
    )
    (net (code "45") (name "/GBE_MDI2_N") (class "Default")
      (node (ref "D12") (pin "1") (pinfunction "IO1_1") (pintype "bidirectional"))
      (node (ref "D12") (pin "10") (pinfunction "NC_10") (pintype "passive"))
      (node (ref "J1") (pin "196") (pinfunction "196_196") (pintype "passive"))
    )
    (net (code "46") (name "/GBE_MDI2_P") (class "Default")
      (node (ref "D12") (pin "2") (pinfunction "IO2_2") (pintype "bidirectional"))
      (node (ref "D12") (pin "9") (pinfunction "NC_9") (pintype "passive"))
      (node (ref "J1") (pin "198") (pinfunction "198_198") (pintype "passive"))
    )
    (net (code "47") (name "/GBE_MDI3_N") (class "Default")
      (node (ref "D12") (pin "4") (pinfunction "IO3_4") (pintype "bidirectional"))
      (node (ref "D12") (pin "7") (pinfunction "NC_7") (pintype "passive"))
      (node (ref "J1") (pin "202") (pinfunction "202_202") (pintype "passive"))
    )
    (net (code "48") (name "/GBE_MDI3_P") (class "Default")
      (node (ref "D12") (pin "5") (pinfunction "IO4_5") (pintype "bidirectional"))
      (node (ref "D12") (pin "6") (pinfunction "NC_6") (pintype "passive"))
      (node (ref "J1") (pin "204") (pinfunction "204_204") (pintype "passive"))
    )
    (net (code "49") (name "/GPIO08_FAN_TACH") (class "Default")
      (node (ref "J1") (pin "208") (pinfunction "208_208") (pintype "passive"))
    )
    (net (code "50") (name "/GPIO09_AUD_MCLK") (class "Default")
      (node (ref "J1") (pin "211") (pinfunction "211_211") (pintype "passive"))
    )
    (net (code "51") (name "/GPIO14_FAN_PWM") (class "Default")
      (node (ref "J1") (pin "230") (pinfunction "230_230") (pintype "passive"))
    )
    (net (code "52") (name "/I2C0_SCL") (class "Default")
      (node (ref "D2") (pin "4") (pinfunction "IO3_4") (pintype "bidirectional"))
      (node (ref "D2") (pin "7") (pinfunction "NC_7") (pintype "passive"))
      (node (ref "J1") (pin "185") (pinfunction "185_185") (pintype "passive"))
    )
    (net (code "53") (name "/I2C0_SDA") (class "Default")
      (node (ref "D2") (pin "5") (pinfunction "IO4_5") (pintype "bidirectional"))
      (node (ref "D2") (pin "6") (pinfunction "NC_6") (pintype "passive"))
      (node (ref "J1") (pin "187") (pinfunction "187_187") (pintype "passive"))
    )
    (net (code "54") (name "/I2S0_DIN") (class "Default")
      (node (ref "D4") (pin "2") (pinfunction "IO2_2") (pintype "bidirectional"))
      (node (ref "D4") (pin "9") (pinfunction "NC_9") (pintype "passive"))
      (node (ref "J1") (pin "195") (pinfunction "195_195") (pintype "passive"))
    )
    (net (code "55") (name "/I2S0_DOUT") (class "Default")
      (node (ref "D4") (pin "1") (pinfunction "IO1_1") (pintype "bidirectional"))
      (node (ref "D4") (pin "10") (pinfunction "NC_10") (pintype "passive"))
      (node (ref "J1") (pin "193") (pinfunction "193_193") (pintype "passive"))
    )
    (net (code "56") (name "/I2S0_FS") (class "Default")
      (node (ref "D4") (pin "4") (pinfunction "IO3_4") (pintype "bidirectional"))
      (node (ref "D4") (pin "7") (pinfunction "NC_7") (pintype "passive"))
      (node (ref "J1") (pin "197") (pinfunction "197_197") (pintype "passive"))
    )
    (net (code "57") (name "/I2S0_SCLK") (class "Default")
      (node (ref "D4") (pin "5") (pinfunction "IO4_5") (pintype "bidirectional"))
      (node (ref "D4") (pin "6") (pinfunction "NC_6") (pintype "passive"))
      (node (ref "J1") (pin "199") (pinfunction "199_199") (pintype "passive"))
    )
    (net (code "58") (name "/PCIE0_CLK_N") (class "Default")
      (node (ref "D18") (pin "1") (pinfunction "IO1_1") (pintype "bidirectional"))
      (node (ref "D18") (pin "10") (pinfunction "NC_10") (pintype "passive"))
      (node (ref "J1") (pin "160") (pinfunction "160_160") (pintype "passive"))
    )
    (net (code "59") (name "/PCIE0_CLK_P") (class "Default")
      (node (ref "D18") (pin "2") (pinfunction "IO2_2") (pintype "bidirectional"))
      (node (ref "D18") (pin "9") (pinfunction "NC_9") (pintype "passive"))
      (node (ref "J1") (pin "162") (pinfunction "162_162") (pintype "passive"))
    )
    (net (code "60") (name "/PCIE0_RX0_N") (class "Default")
      (node (ref "D10") (pin "1") (pinfunction "IO1_1") (pintype "bidirectional"))
      (node (ref "D10") (pin "10") (pinfunction "NC_10") (pintype "passive"))
      (node (ref "J1") (pin "131") (pinfunction "131_131") (pintype "passive"))
    )
    (net (code "61") (name "/PCIE0_RX0_P") (class "Default")
      (node (ref "D10") (pin "2") (pinfunction "IO2_2") (pintype "bidirectional"))
      (node (ref "D10") (pin "9") (pinfunction "NC_9") (pintype "passive"))
      (node (ref "J1") (pin "133") (pinfunction "133_133") (pintype "passive"))
    )
    (net (code "62") (name "/PCIE0_RX1_N") (class "Default")
      (node (ref "D10") (pin "4") (pinfunction "IO3_4") (pintype "bidirectional"))
      (node (ref "D10") (pin "7") (pinfunction "NC_7") (pintype "passive"))
      (node (ref "J1") (pin "137") (pinfunction "137_137") (pintype "passive"))
    )
    (net (code "63") (name "/PCIE0_RX1_P") (class "Default")
      (node (ref "D10") (pin "5") (pinfunction "IO4_5") (pintype "bidirectional"))
      (node (ref "D10") (pin "6") (pinfunction "NC_6") (pintype "passive"))
      (node (ref "J1") (pin "139") (pinfunction "139_139") (pintype "passive"))
    )
    (net (code "64") (name "/PCIE0_RX2_N") (class "Default")
      (node (ref "D17") (pin "1") (pinfunction "IO1_1") (pintype "bidirectional"))
      (node (ref "D17") (pin "10") (pinfunction "NC_10") (pintype "passive"))
      (node (ref "J1") (pin "149") (pinfunction "149_149") (pintype "passive"))
    )
    (net (code "65") (name "/PCIE0_RX2_P") (class "Default")
      (node (ref "D17") (pin "2") (pinfunction "IO2_2") (pintype "bidirectional"))
      (node (ref "D17") (pin "9") (pinfunction "NC_9") (pintype "passive"))
      (node (ref "J1") (pin "151") (pinfunction "151_151") (pintype "passive"))
    )
    (net (code "66") (name "/PCIE0_RX3_N") (class "Default")
      (node (ref "D17") (pin "4") (pinfunction "IO3_4") (pintype "bidirectional"))
      (node (ref "D17") (pin "7") (pinfunction "NC_7") (pintype "passive"))
      (node (ref "J1") (pin "155") (pinfunction "155_155") (pintype "passive"))
    )
    (net (code "67") (name "/PCIE0_RX3_P") (class "Default")
      (node (ref "D17") (pin "5") (pinfunction "IO4_5") (pintype "bidirectional"))
      (node (ref "D17") (pin "6") (pinfunction "NC_6") (pintype "passive"))
      (node (ref "J1") (pin "157") (pinfunction "157_157") (pintype "passive"))
    )
    (net (code "68") (name "/PCIE0_TX0_N") (class "Default")
      (node (ref "D21") (pin "1") (pinfunction "IO1_1") (pintype "bidirectional"))
      (node (ref "D21") (pin "10") (pinfunction "NC_10") (pintype "passive"))
      (node (ref "J1") (pin "134") (pinfunction "134_134") (pintype "passive"))
    )
    (net (code "69") (name "/PCIE0_TX0_P") (class "Default")
      (node (ref "D21") (pin "2") (pinfunction "IO2_2") (pintype "bidirectional"))
      (node (ref "D21") (pin "9") (pinfunction "NC_9") (pintype "passive"))
      (node (ref "J1") (pin "136") (pinfunction "136_136") (pintype "passive"))
    )
    (net (code "70") (name "/PCIE0_TX1_N") (class "Default")
      (node (ref "D21") (pin "4") (pinfunction "IO3_4") (pintype "bidirectional"))
      (node (ref "D21") (pin "7") (pinfunction "NC_7") (pintype "passive"))
      (node (ref "J1") (pin "140") (pinfunction "140_140") (pintype "passive"))
    )
    (net (code "71") (name "/PCIE0_TX1_P") (class "Default")
      (node (ref "D21") (pin "5") (pinfunction "IO4_5") (pintype "bidirectional"))
      (node (ref "D21") (pin "6") (pinfunction "NC_6") (pintype "passive"))
      (node (ref "J1") (pin "142") (pinfunction "142_142") (pintype "passive"))
    )
    (net (code "72") (name "/PCIE0_TX2_N") (class "Default")
      (node (ref "D11") (pin "1") (pinfunction "IO1_1") (pintype "bidirectional"))
      (node (ref "D11") (pin "10") (pinfunction "NC_10") (pintype "passive"))
      (node (ref "J1") (pin "148") (pinfunction "148_148") (pintype "passive"))
    )
    (net (code "73") (name "/PCIE0_TX2_P") (class "Default")
      (node (ref "D11") (pin "2") (pinfunction "IO2_2") (pintype "bidirectional"))
      (node (ref "D11") (pin "9") (pinfunction "NC_9") (pintype "passive"))
      (node (ref "J1") (pin "150") (pinfunction "150_150") (pintype "passive"))
    )
    (net (code "74") (name "/PCIE0_TX3_N") (class "Default")
      (node (ref "D11") (pin "4") (pinfunction "IO3_4") (pintype "bidirectional"))
      (node (ref "D11") (pin "7") (pinfunction "NC_7") (pintype "passive"))
      (node (ref "J1") (pin "154") (pinfunction "154_154") (pintype "passive"))
    )
    (net (code "75") (name "/PCIE0_TX3_P") (class "Default")
      (node (ref "D11") (pin "5") (pinfunction "IO4_5") (pintype "bidirectional"))
      (node (ref "D11") (pin "6") (pinfunction "NC_6") (pintype "passive"))
      (node (ref "J1") (pin "156") (pinfunction "156_156") (pintype "passive"))
    )
    (net (code "76") (name "/PCIE0_nCLKREQ") (class "Default")
      (node (ref "J1") (pin "180") (pinfunction "180_180") (pintype "passive"))
    )
    (net (code "77") (name "/PCIE0_nRST") (class "Default")
      (node (ref "D2") (pin "2") (pinfunction "IO2_2") (pintype "bidirectional"))
      (node (ref "D2") (pin "9") (pinfunction "NC_9") (pintype "passive"))
      (node (ref "J1") (pin "181") (pinfunction "181_181") (pintype "passive"))
    )
    (net (code "78") (name "/PCIE_32K_CLK") (class "Default")
      (node (ref "J1") (pin "210") (pinfunction "210_210") (pintype "passive"))
    )
    (net (code "79") (name "/PCIE_WAKE") (class "Default")
      (node (ref "D2") (pin "1") (pinfunction "IO1_1") (pintype "bidirectional"))
      (node (ref "D2") (pin "10") (pinfunction "NC_10") (pintype "passive"))
      (node (ref "J1") (pin "179") (pinfunction "179_179") (pintype "passive"))
    )
    (net (code "80") (name "/POWER_EN") (class "Default")
      (node (ref "J1") (pin "237") (pinfunction "237_237") (pintype "passive"))
    )
    (net (code "81") (name "/PRE_CSI0_D1_N") (class "Default")
      (node (ref "D13") (pin "1") (pinfunction "IO1_1") (pintype "bidirectional"))
      (node (ref "D13") (pin "10") (pinfunction "NC_10") (pintype "passive"))
      (node (ref "J1") (pin "16") (pinfunction "16_16") (pintype "passive"))
      (node (ref "R3") (pin "1") (pinfunction "1_1") (pintype "passive"))
    )
    (net (code "82") (name "/PRE_CSI0_D1_P") (class "Default")
      (node (ref "D13") (pin "2") (pinfunction "IO2_2") (pintype "bidirectional"))
      (node (ref "D13") (pin "9") (pinfunction "NC_9") (pintype "passive"))
      (node (ref "J1") (pin "18") (pinfunction "18_18") (pintype "passive"))
      (node (ref "R4") (pin "1") (pinfunction "1_1") (pintype "passive"))
    )
    (net (code "83") (name "/PRE_CSI1_D0_N") (class "Default")
      (node (ref "D7") (pin "1") (pinfunction "IO1_1") (pintype "bidirectional"))
      (node (ref "D7") (pin "10") (pinfunction "NC_10") (pintype "passive"))
      (node (ref "J1") (pin "3") (pinfunction "3_3") (pintype "passive"))
      (node (ref "R1") (pin "1") (pinfunction "1_1") (pintype "passive"))
    )
    (net (code "84") (name "/PRE_CSI1_D0_P") (class "Default")
      (node (ref "D7") (pin "2") (pinfunction "IO2_2") (pintype "bidirectional"))
      (node (ref "D7") (pin "9") (pinfunction "NC_9") (pintype "passive"))
      (node (ref "J1") (pin "5") (pinfunction "5_5") (pintype "passive"))
      (node (ref "R2") (pin "1") (pinfunction "1_1") (pintype "passive"))
    )
    (net (code "85") (name "/REC_USB_VBUS") (class "Default")
      (node (ref "Q6") (pin "1") (pinfunction "G_1") (pintype "passive"))
      (node (ref "R22") (pin "2") (pinfunction "2_2") (pintype "passive"))
    )
    (net (code "86") (name "/SPI0_MISO") (class "Default")
      (node (ref "D1") (pin "4") (pinfunction "IO3_4") (pintype "bidirectional"))
      (node (ref "D1") (pin "7") (pinfunction "NC_7") (pintype "passive"))
      (node (ref "J1") (pin "93") (pinfunction "93_93") (pintype "passive"))
    )
    (net (code "87") (name "/SPI0_MOSI") (class "Default")
      (node (ref "D1") (pin "1") (pinfunction "IO1_1") (pintype "bidirectional"))
      (node (ref "D1") (pin "10") (pinfunction "NC_10") (pintype "passive"))
      (node (ref "J1") (pin "89") (pinfunction "89_89") (pintype "passive"))
    )
    (net (code "88") (name "/SPI0_SCLK") (class "Default")
      (node (ref "D1") (pin "2") (pinfunction "IO2_2") (pintype "bidirectional"))
      (node (ref "D1") (pin "9") (pinfunction "NC_9") (pintype "passive"))
      (node (ref "J1") (pin "91") (pinfunction "91_91") (pintype "passive"))
    )
    (net (code "89") (name "/SPI0_nCS_0") (class "Default")
      (node (ref "D1") (pin "5") (pinfunction "IO4_5") (pintype "bidirectional"))
      (node (ref "D1") (pin "6") (pinfunction "NC_6") (pintype "passive"))
      (node (ref "J1") (pin "95") (pinfunction "95_95") (pintype "passive"))
    )
    (net (code "90") (name "/SPI0_nCS_1") (class "Default")
      (node (ref "J1") (pin "97") (pinfunction "97_97") (pintype "passive"))
    )
    (net (code "91") (name "/SPI1_MISO") (class "Default")
      (node (ref "D3") (pin "4") (pinfunction "IO3_4") (pintype "bidirectional"))
      (node (ref "D3") (pin "7") (pinfunction "NC_7") (pintype "passive"))
      (node (ref "J1") (pin "108") (pinfunction "108_108") (pintype "passive"))
    )
    (net (code "92") (name "/SPI1_MOSI") (class "Default")
      (node (ref "D3") (pin "1") (pinfunction "IO1_1") (pintype "bidirectional"))
      (node (ref "D3") (pin "10") (pinfunction "NC_10") (pintype "passive"))
      (node (ref "J1") (pin "104") (pinfunction "104_104") (pintype "passive"))
    )
    (net (code "93") (name "/SPI1_SCLK") (class "Default")
      (node (ref "D3") (pin "2") (pinfunction "IO2_2") (pintype "bidirectional"))
      (node (ref "D3") (pin "9") (pinfunction "NC_9") (pintype "passive"))
      (node (ref "J1") (pin "106") (pinfunction "106_106") (pintype "passive"))
    )
    (net (code "94") (name "/SPI1_nCS_0") (class "Default")
      (node (ref "D3") (pin "5") (pinfunction "IO4_5") (pintype "bidirectional"))
      (node (ref "D3") (pin "6") (pinfunction "NC_6") (pintype "passive"))
      (node (ref "J1") (pin "110") (pinfunction "110_110") (pintype "passive"))
    )
    (net (code "95") (name "/SPI1_nCS_1") (class "Default")
      (node (ref "J1") (pin "112") (pinfunction "112_112") (pintype "passive"))
    )
    (net (code "96") (name "/USB0_D_N") (class "Default")
      (node (ref "D9") (pin "1") (pinfunction "IO1_1") (pintype "bidirectional"))
      (node (ref "D9") (pin "10") (pinfunction "NC_10") (pintype "passive"))
      (node (ref "J1") (pin "109") (pinfunction "109_109") (pintype "passive"))
    )
    (net (code "97") (name "/USB0_D_P") (class "Default")
      (node (ref "D9") (pin "2") (pinfunction "IO2_2") (pintype "bidirectional"))
      (node (ref "D9") (pin "9") (pinfunction "NC_9") (pintype "passive"))
      (node (ref "J1") (pin "111") (pinfunction "111_111") (pintype "passive"))
    )
    (net (code "98") (name "/USB1_D_N") (class "Default")
      (node (ref "D9") (pin "4") (pinfunction "IO3_4") (pintype "bidirectional"))
      (node (ref "D9") (pin "7") (pinfunction "NC_7") (pintype "passive"))
      (node (ref "J1") (pin "115") (pinfunction "115_115") (pintype "passive"))
    )
    (net (code "99") (name "/USB1_D_P") (class "Default")
      (node (ref "D9") (pin "5") (pinfunction "IO4_5") (pintype "bidirectional"))
      (node (ref "D9") (pin "6") (pinfunction "NC_6") (pintype "passive"))
      (node (ref "J1") (pin "117") (pinfunction "117_117") (pintype "passive"))
    )
    (net (code "100") (name "/USBSS0_RX_N") (class "Default")
      (node (ref "D16") (pin "1") (pinfunction "IO1_1") (pintype "bidirectional"))
      (node (ref "D16") (pin "10") (pinfunction "NC_10") (pintype "passive"))
      (node (ref "J1") (pin "161") (pinfunction "161_161") (pintype "passive"))
    )
    (net (code "101") (name "/USBSS0_RX_P") (class "Default")
      (node (ref "D16") (pin "2") (pinfunction "IO2_2") (pintype "bidirectional"))
      (node (ref "D16") (pin "9") (pinfunction "NC_9") (pintype "passive"))
      (node (ref "J1") (pin "163") (pinfunction "163_163") (pintype "passive"))
    )
    (net (code "102") (name "/USBSS0_TX_N") (class "Default")
      (node (ref "D16") (pin "4") (pinfunction "IO3_4") (pintype "bidirectional"))
      (node (ref "D16") (pin "7") (pinfunction "NC_7") (pintype "passive"))
      (node (ref "J1") (pin "166") (pinfunction "166_166") (pintype "passive"))
    )
    (net (code "103") (name "/USBSS0_TX_P") (class "Default")
      (node (ref "D16") (pin "5") (pinfunction "IO4_5") (pintype "bidirectional"))
      (node (ref "D16") (pin "6") (pinfunction "NC_6") (pintype "passive"))
      (node (ref "J1") (pin "168") (pinfunction "168_168") (pintype "passive"))
    )
    (net (code "104") (name "/VBUS_DETECT") (class "Default")
      (node (ref "J1") (pin "87") (pinfunction "87_87") (pintype "passive"))
      (node (ref "R23") (pin "2") (pinfunction "2_2") (pintype "passive"))
    )
    (net (code "105") (name "/nFORCE_RECOVERY") (class "Default")
      (node (ref "J1") (pin "214") (pinfunction "214_214") (pintype "passive"))
    )
    (net (code "106") (name "/nMOD_SLEEP") (class "Default")
      (node (ref "J1") (pin "178") (pinfunction "178_178") (pintype "passive"))
    )
    (net (code "107") (name "/nSHUTDOWN_REQ") (class "Default")
      (node (ref "J1") (pin "233") (pinfunction "233_233") (pintype "passive"))
    )
    (net (code "108") (name "/nSYS_RESET") (class "Default")
      (node (ref "J1") (pin "239") (pinfunction "239_239") (pintype "passive"))
    )
    (net (code "109") (name "5V_MAIN") (class "Default")
      (node (ref "J1") (pin "251") (pinfunction "251_251") (pintype "passive"))
      (node (ref "J1") (pin "252") (pinfunction "252_252") (pintype "passive"))
      (node (ref "J1") (pin "253") (pinfunction "253_253") (pintype "passive"))
      (node (ref "J1") (pin "254") (pinfunction "254_254") (pintype "passive"))
      (node (ref "J1") (pin "255") (pinfunction "255_255") (pintype "passive"))
      (node (ref "J1") (pin "256") (pinfunction "256_256") (pintype "passive"))
      (node (ref "J1") (pin "257") (pinfunction "257_257") (pintype "passive"))
      (node (ref "J1") (pin "258") (pinfunction "258_258") (pintype "passive"))
      (node (ref "J1") (pin "259") (pinfunction "259_259") (pintype "passive"))
      (node (ref "J1") (pin "260") (pinfunction "260_260") (pintype "passive"))
    )
    (net (code "110") (name "GND") (class "Default")
      (node (ref "D1") (pin "3") (pinfunction "GND_3") (pintype "power_in"))
      (node (ref "D1") (pin "8") (pinfunction "GND_8") (pintype "power_in"))
      (node (ref "D10") (pin "3") (pinfunction "GND_3") (pintype "power_in"))
      (node (ref "D10") (pin "8") (pinfunction "GND_8") (pintype "power_in"))
      (node (ref "D11") (pin "3") (pinfunction "GND_3") (pintype "power_in"))
      (node (ref "D11") (pin "8") (pinfunction "GND_8") (pintype "power_in"))
      (node (ref "D12") (pin "3") (pinfunction "GND_3") (pintype "power_in"))
      (node (ref "D12") (pin "8") (pinfunction "GND_8") (pintype "power_in"))
      (node (ref "D13") (pin "3") (pinfunction "GND_3") (pintype "power_in"))
      (node (ref "D13") (pin "8") (pinfunction "GND_8") (pintype "power_in"))
      (node (ref "D14") (pin "3") (pinfunction "GND_3") (pintype "power_in"))
      (node (ref "D14") (pin "8") (pinfunction "GND_8") (pintype "power_in"))
      (node (ref "D15") (pin "3") (pinfunction "GND_3") (pintype "power_in"))
      (node (ref "D15") (pin "8") (pinfunction "GND_8") (pintype "power_in"))
      (node (ref "D16") (pin "3") (pinfunction "GND_3") (pintype "power_in"))
      (node (ref "D16") (pin "8") (pinfunction "GND_8") (pintype "power_in"))
      (node (ref "D17") (pin "3") (pinfunction "GND_3") (pintype "power_in"))
      (node (ref "D17") (pin "8") (pinfunction "GND_8") (pintype "power_in"))
      (node (ref "D18") (pin "3") (pinfunction "GND_3") (pintype "power_in"))
      (node (ref "D18") (pin "8") (pinfunction "GND_8") (pintype "power_in"))
      (node (ref "D19") (pin "3") (pinfunction "GND_3") (pintype "power_in"))
      (node (ref "D19") (pin "8") (pinfunction "GND_8") (pintype "power_in"))
      (node (ref "D2") (pin "3") (pinfunction "GND_3") (pintype "power_in"))
      (node (ref "D2") (pin "8") (pinfunction "GND_8") (pintype "power_in"))
      (node (ref "D20") (pin "3") (pinfunction "GND_3") (pintype "power_in"))
      (node (ref "D20") (pin "8") (pinfunction "GND_8") (pintype "power_in"))
      (node (ref "D21") (pin "3") (pinfunction "GND_3") (pintype "power_in"))
      (node (ref "D21") (pin "8") (pinfunction "GND_8") (pintype "power_in"))
      (node (ref "D3") (pin "3") (pinfunction "GND_3") (pintype "power_in"))
      (node (ref "D3") (pin "8") (pinfunction "GND_8") (pintype "power_in"))
      (node (ref "D4") (pin "3") (pinfunction "GND_3") (pintype "power_in"))
      (node (ref "D4") (pin "8") (pinfunction "GND_8") (pintype "power_in"))
      (node (ref "D5") (pin "3") (pinfunction "GND_3") (pintype "power_in"))
      (node (ref "D5") (pin "8") (pinfunction "GND_8") (pintype "power_in"))
      (node (ref "D6") (pin "3") (pinfunction "GND_3") (pintype "power_in"))
      (node (ref "D6") (pin "8") (pinfunction "GND_8") (pintype "power_in"))
      (node (ref "D7") (pin "3") (pinfunction "GND_3") (pintype "power_in"))
      (node (ref "D7") (pin "8") (pinfunction "GND_8") (pintype "power_in"))
      (node (ref "D8") (pin "3") (pinfunction "GND_3") (pintype "power_in"))
      (node (ref "D8") (pin "8") (pinfunction "GND_8") (pintype "power_in"))
      (node (ref "D9") (pin "3") (pinfunction "GND_3") (pintype "power_in"))
      (node (ref "D9") (pin "8") (pinfunction "GND_8") (pintype "power_in"))
      (node (ref "J1") (pin "1") (pinfunction "1_1") (pintype "passive"))
      (node (ref "J1") (pin "102") (pinfunction "102_102") (pintype "passive"))
      (node (ref "J1") (pin "107") (pinfunction "107_107") (pintype "passive"))
      (node (ref "J1") (pin "113") (pinfunction "113_113") (pintype "passive"))
      (node (ref "J1") (pin "119") (pinfunction "119_119") (pintype "passive"))
      (node (ref "J1") (pin "125") (pinfunction "125_125") (pintype "passive"))
      (node (ref "J1") (pin "129") (pinfunction "129_129") (pintype "passive"))
      (node (ref "J1") (pin "13") (pinfunction "13_13") (pintype "passive"))
      (node (ref "J1") (pin "132") (pinfunction "132_132") (pintype "passive"))
      (node (ref "J1") (pin "135") (pinfunction "135_135") (pintype "passive"))
      (node (ref "J1") (pin "138") (pinfunction "138_138") (pintype "passive"))
      (node (ref "J1") (pin "14") (pinfunction "14_14") (pintype "passive"))
      (node (ref "J1") (pin "141") (pinfunction "141_141") (pintype "passive"))
      (node (ref "J1") (pin "144") (pinfunction "144_144") (pintype "passive"))
      (node (ref "J1") (pin "146") (pinfunction "146_146") (pintype "passive"))
      (node (ref "J1") (pin "147") (pinfunction "147_147") (pintype "passive"))
      (node (ref "J1") (pin "152") (pinfunction "152_152") (pintype "passive"))
      (node (ref "J1") (pin "153") (pinfunction "153_153") (pintype "passive"))
      (node (ref "J1") (pin "158") (pinfunction "158_158") (pintype "passive"))
      (node (ref "J1") (pin "159") (pinfunction "159_159") (pintype "passive"))
      (node (ref "J1") (pin "164") (pinfunction "164_164") (pintype "passive"))
      (node (ref "J1") (pin "165") (pinfunction "165_165") (pintype "passive"))
      (node (ref "J1") (pin "170") (pinfunction "170_170") (pintype "passive"))
      (node (ref "J1") (pin "171") (pinfunction "171_171") (pintype "passive"))
      (node (ref "J1") (pin "176") (pinfunction "176_176") (pintype "passive"))
      (node (ref "J1") (pin "177") (pinfunction "177_177") (pintype "passive"))
      (node (ref "J1") (pin "19") (pinfunction "19_19") (pintype "passive"))
      (node (ref "J1") (pin "2") (pinfunction "2_2") (pintype "passive"))
      (node (ref "J1") (pin "20") (pinfunction "20_20") (pintype "passive"))
      (node (ref "J1") (pin "200") (pinfunction "200_200") (pintype "passive"))
      (node (ref "J1") (pin "201") (pinfunction "201_201") (pintype "passive"))
      (node (ref "J1") (pin "231") (pinfunction "231_231") (pintype "passive"))
      (node (ref "J1") (pin "241") (pinfunction "241_241") (pintype "passive"))
      (node (ref "J1") (pin "242") (pinfunction "242_242") (pintype "passive"))
      (node (ref "J1") (pin "243") (pinfunction "243_243") (pintype "passive"))
      (node (ref "J1") (pin "244") (pinfunction "244_244") (pintype "passive"))
      (node (ref "J1") (pin "245") (pinfunction "245_245") (pintype "passive"))
      (node (ref "J1") (pin "246") (pinfunction "246_246") (pintype "passive"))
      (node (ref "J1") (pin "247") (pinfunction "247_247") (pintype "passive"))
      (node (ref "J1") (pin "248") (pinfunction "248_248") (pintype "passive"))
      (node (ref "J1") (pin "249") (pinfunction "249_249") (pintype "passive"))
      (node (ref "J1") (pin "25") (pinfunction "25_25") (pintype "passive"))
      (node (ref "J1") (pin "250") (pinfunction "250_250") (pintype "passive"))
      (node (ref "J1") (pin "26") (pinfunction "26_26") (pintype "passive"))
      (node (ref "J1") (pin "261") (pinfunction "MNT_1_261") (pintype "passive"))
      (node (ref "J1") (pin "262") (pinfunction "MNT_2_262") (pintype "passive"))
      (node (ref "J1") (pin "31") (pinfunction "31_31") (pintype "passive"))
      (node (ref "J1") (pin "32") (pinfunction "32_32") (pintype "passive"))
      (node (ref "J1") (pin "37") (pinfunction "37_37") (pintype "passive"))
      (node (ref "J1") (pin "38") (pinfunction "38_38") (pintype "passive"))
      (node (ref "J1") (pin "43") (pinfunction "43_43") (pintype "passive"))
      (node (ref "J1") (pin "44") (pinfunction "44_44") (pintype "passive"))
      (node (ref "J1") (pin "49") (pinfunction "49_49") (pintype "passive"))
      (node (ref "J1") (pin "50") (pinfunction "50_50") (pintype "passive"))
      (node (ref "J1") (pin "55") (pinfunction "55_55") (pintype "passive"))
      (node (ref "J1") (pin "56") (pinfunction "56_56") (pintype "passive"))
      (node (ref "J1") (pin "61") (pinfunction "61_61") (pintype "passive"))
      (node (ref "J1") (pin "62") (pinfunction "62_62") (pintype "passive"))
      (node (ref "J1") (pin "67") (pinfunction "67_67") (pintype "passive"))
      (node (ref "J1") (pin "68") (pinfunction "68_68") (pintype "passive"))
      (node (ref "J1") (pin "7") (pinfunction "7_7") (pintype "passive"))
      (node (ref "J1") (pin "73") (pinfunction "73_73") (pintype "passive"))
      (node (ref "J1") (pin "74") (pinfunction "74_74") (pintype "passive"))
      (node (ref "J1") (pin "79") (pinfunction "79_79") (pintype "passive"))
      (node (ref "J1") (pin "8") (pinfunction "8_8") (pintype "passive"))
      (node (ref "J1") (pin "80") (pinfunction "80_80") (pintype "passive"))
      (node (ref "J1") (pin "85") (pinfunction "85_85") (pintype "passive"))
      (node (ref "J1") (pin "86") (pinfunction "86_86") (pintype "passive"))
      (node (ref "MP2") (pin "1") (pinfunction "1_1") (pintype "passive"))
      (node (ref "MP3") (pin "1") (pinfunction "1_1") (pintype "passive"))
      (node (ref "Q6") (pin "2") (pinfunction "S_2") (pintype "passive"))
      (node (ref "R22") (pin "1") (pinfunction "1_1") (pintype "passive"))
    )
    (net (code "111") (name "Net-(Q6-D)") (class "Default")
      (node (ref "Q6") (pin "3") (pinfunction "D_3") (pintype "passive"))
      (node (ref "R23") (pin "1") (pinfunction "1_1") (pintype "passive"))
    )
    (net (code "112") (name "unconnected-(J1-Pad9)") (class "Default")
      (node (ref "J1") (pin "9") (pinfunction "9_9") (pintype "passive+no_connect"))
    )
    (net (code "113") (name "unconnected-(J1-Pad11)") (class "Default")
      (node (ref "J1") (pin "11") (pinfunction "11_11") (pintype "passive+no_connect"))
    )
    (net (code "114") (name "unconnected-(J1-Pad27)") (class "Default")
      (node (ref "J1") (pin "27") (pinfunction "27_27") (pintype "passive+no_connect"))
    )
    (net (code "115") (name "unconnected-(J1-Pad29)") (class "Default")
      (node (ref "J1") (pin "29") (pinfunction "29_29") (pintype "passive+no_connect"))
    )
    (net (code "116") (name "unconnected-(J1-Pad39)") (class "Default")
      (node (ref "J1") (pin "39") (pinfunction "39_39") (pintype "passive+no_connect"))
    )
    (net (code "117") (name "unconnected-(J1-Pad40)") (class "Default")
      (node (ref "J1") (pin "40") (pinfunction "40_40") (pintype "passive+no_connect"))
    )
    (net (code "118") (name "unconnected-(J1-Pad41)") (class "Default")
      (node (ref "J1") (pin "41") (pinfunction "41_41") (pintype "passive+no_connect"))
    )
    (net (code "119") (name "unconnected-(J1-Pad42)") (class "Default")
      (node (ref "J1") (pin "42") (pinfunction "42_42") (pintype "passive+no_connect"))
    )
    (net (code "120") (name "unconnected-(J1-Pad45)") (class "Default")
      (node (ref "J1") (pin "45") (pinfunction "45_45") (pintype "passive+no_connect"))
    )
    (net (code "121") (name "unconnected-(J1-Pad46)") (class "Default")
      (node (ref "J1") (pin "46") (pinfunction "46_46") (pintype "passive+no_connect"))
    )
    (net (code "122") (name "unconnected-(J1-Pad47)") (class "Default")
      (node (ref "J1") (pin "47") (pinfunction "47_47") (pintype "passive+no_connect"))
    )
    (net (code "123") (name "unconnected-(J1-Pad48)") (class "Default")
      (node (ref "J1") (pin "48") (pinfunction "48_48") (pintype "passive+no_connect"))
    )
    (net (code "124") (name "unconnected-(J1-Pad51)") (class "Default")
      (node (ref "J1") (pin "51") (pinfunction "51_51") (pintype "passive+no_connect"))
    )
    (net (code "125") (name "unconnected-(J1-Pad52)") (class "Default")
      (node (ref "J1") (pin "52") (pinfunction "52_52") (pintype "passive+no_connect"))
    )
    (net (code "126") (name "unconnected-(J1-Pad53)") (class "Default")
      (node (ref "J1") (pin "53") (pinfunction "53_53") (pintype "passive+no_connect"))
    )
    (net (code "127") (name "unconnected-(J1-Pad54)") (class "Default")
      (node (ref "J1") (pin "54") (pinfunction "54_54") (pintype "passive+no_connect"))
    )
    (net (code "128") (name "unconnected-(J1-Pad57)") (class "Default")
      (node (ref "J1") (pin "57") (pinfunction "57_57") (pintype "passive+no_connect"))
    )
    (net (code "129") (name "unconnected-(J1-Pad58)") (class "Default")
      (node (ref "J1") (pin "58") (pinfunction "58_58") (pintype "passive+no_connect"))
    )
    (net (code "130") (name "unconnected-(J1-Pad59)") (class "Default")
      (node (ref "J1") (pin "59") (pinfunction "59_59") (pintype "passive+no_connect"))
    )
    (net (code "131") (name "unconnected-(J1-Pad60)") (class "Default")
      (node (ref "J1") (pin "60") (pinfunction "60_60") (pintype "passive+no_connect"))
    )
    (net (code "132") (name "unconnected-(J1-Pad64)") (class "Default")
      (node (ref "J1") (pin "64") (pinfunction "64_64") (pintype "passive+no_connect"))
    )
    (net (code "133") (name "unconnected-(J1-Pad66)") (class "Default")
      (node (ref "J1") (pin "66") (pinfunction "66_66") (pintype "passive+no_connect"))
    )
    (net (code "134") (name "unconnected-(J1-Pad70)") (class "Default")
      (node (ref "J1") (pin "70") (pinfunction "70_70") (pintype "passive+no_connect"))
    )
    (net (code "135") (name "unconnected-(J1-Pad72)") (class "Default")
      (node (ref "J1") (pin "72") (pinfunction "72_72") (pintype "passive+no_connect"))
    )
    (net (code "136") (name "unconnected-(J1-Pad76)") (class "Default")
      (node (ref "J1") (pin "76") (pinfunction "76_76") (pintype "passive+no_connect"))
    )
    (net (code "137") (name "unconnected-(J1-Pad78)") (class "Default")
      (node (ref "J1") (pin "78") (pinfunction "78_78") (pintype "passive+no_connect"))
    )
    (net (code "138") (name "unconnected-(J1-Pad82)") (class "Default")
      (node (ref "J1") (pin "82") (pinfunction "82_82") (pintype "passive+no_connect"))
    )
    (net (code "139") (name "unconnected-(J1-Pad84)") (class "Default")
      (node (ref "J1") (pin "84") (pinfunction "84_84") (pintype "passive+no_connect"))
    )
    (net (code "140") (name "unconnected-(J1-Pad88)") (class "Default")
      (node (ref "J1") (pin "88") (pinfunction "88_88") (pintype "passive+no_connect"))
    )
    (net (code "141") (name "unconnected-(J1-Pad90)") (class "Default")
      (node (ref "J1") (pin "90") (pinfunction "90_90") (pintype "passive+no_connect"))
    )
    (net (code "142") (name "unconnected-(J1-Pad92)") (class "Default")
      (node (ref "J1") (pin "92") (pinfunction "92_92") (pintype "passive+no_connect"))
    )
    (net (code "143") (name "unconnected-(J1-Pad99)") (class "Default")
      (node (ref "J1") (pin "99") (pinfunction "99_99") (pintype "passive+no_connect"))
    )
    (net (code "144") (name "unconnected-(J1-Pad101)") (class "Default")
      (node (ref "J1") (pin "101") (pinfunction "101_101") (pintype "passive+no_connect"))
    )
    (net (code "145") (name "unconnected-(J1-Pad103)") (class "Default")
      (node (ref "J1") (pin "103") (pinfunction "103_103") (pintype "passive+no_connect"))
    )
    (net (code "146") (name "unconnected-(J1-Pad105)") (class "Default")
      (node (ref "J1") (pin "105") (pinfunction "105_105") (pintype "passive+no_connect"))
    )
    (net (code "147") (name "unconnected-(J1-Pad114)") (class "Default")
      (node (ref "J1") (pin "114") (pinfunction "114_114") (pintype "passive+no_connect"))
    )
    (net (code "148") (name "unconnected-(J1-Pad118)") (class "Default")
      (node (ref "J1") (pin "118") (pinfunction "118_118") (pintype "passive+no_connect"))
    )
    (net (code "149") (name "unconnected-(J1-Pad121)") (class "Default")
      (node (ref "J1") (pin "121") (pinfunction "121_121") (pintype "passive+no_connect"))
    )
    (net (code "150") (name "unconnected-(J1-Pad122)") (class "Default")
      (node (ref "J1") (pin "122") (pinfunction "122_122") (pintype "passive+no_connect"))
    )
    (net (code "151") (name "unconnected-(J1-Pad123)") (class "Default")
      (node (ref "J1") (pin "123") (pinfunction "123_123") (pintype "passive+no_connect"))
    )
    (net (code "152") (name "unconnected-(J1-Pad124)") (class "Default")
      (node (ref "J1") (pin "124") (pinfunction "124_124") (pintype "passive+no_connect"))
    )
    (net (code "153") (name "unconnected-(J1-Pad126)") (class "Default")
      (node (ref "J1") (pin "126") (pinfunction "126_126") (pintype "passive+no_connect"))
    )
    (net (code "154") (name "unconnected-(J1-Pad127)") (class "Default")
      (node (ref "J1") (pin "127") (pinfunction "127_127") (pintype "passive+no_connect"))
    )
    (net (code "155") (name "unconnected-(J1-Pad128)") (class "Default")
      (node (ref "J1") (pin "128") (pinfunction "128_128") (pintype "passive+no_connect"))
    )
    (net (code "156") (name "unconnected-(J1-Pad130)") (class "Default")
      (node (ref "J1") (pin "130") (pinfunction "130_130") (pintype "passive+no_connect"))
    )
    (net (code "157") (name "unconnected-(J1-Pad167)") (class "Default")
      (node (ref "J1") (pin "167") (pinfunction "167_167") (pintype "passive+no_connect"))
    )
    (net (code "158") (name "unconnected-(J1-Pad169)") (class "Default")
      (node (ref "J1") (pin "169") (pinfunction "169_169") (pintype "passive+no_connect"))
    )
    (net (code "159") (name "unconnected-(J1-Pad172)") (class "Default")
      (node (ref "J1") (pin "172") (pinfunction "172_172") (pintype "passive+no_connect"))
    )
    (net (code "160") (name "unconnected-(J1-Pad173)") (class "Default")
      (node (ref "J1") (pin "173") (pinfunction "173_173") (pintype "passive+no_connect"))
    )
    (net (code "161") (name "unconnected-(J1-Pad174)") (class "Default")
      (node (ref "J1") (pin "174") (pinfunction "174_174") (pintype "passive+no_connect"))
    )
    (net (code "162") (name "unconnected-(J1-Pad175)") (class "Default")
      (node (ref "J1") (pin "175") (pinfunction "175_175") (pintype "passive+no_connect"))
    )
    (net (code "163") (name "unconnected-(J1-Pad182)") (class "Default")
      (node (ref "J1") (pin "182") (pinfunction "182_182") (pintype "passive+no_connect"))
    )
    (net (code "164") (name "unconnected-(J1-Pad183)") (class "Default")
      (node (ref "J1") (pin "183") (pinfunction "183_183") (pintype "passive+no_connect"))
    )
    (net (code "165") (name "unconnected-(J1-Pad189)") (class "Default")
      (node (ref "J1") (pin "189") (pinfunction "189_189") (pintype "passive+no_connect"))
    )
    (net (code "166") (name "unconnected-(J1-Pad191)") (class "Default")
      (node (ref "J1") (pin "191") (pinfunction "191_191") (pintype "passive+no_connect"))
    )
    (net (code "167") (name "unconnected-(J1-Pad203)") (class "Default")
      (node (ref "J1") (pin "203") (pinfunction "203_203") (pintype "passive+no_connect"))
    )
    (net (code "168") (name "unconnected-(J1-Pad205)") (class "Default")
      (node (ref "J1") (pin "205") (pinfunction "205_205") (pintype "passive+no_connect"))
    )
    (net (code "169") (name "unconnected-(J1-Pad206)") (class "Default")
      (node (ref "J1") (pin "206") (pinfunction "206_206") (pintype "passive+no_connect"))
    )
    (net (code "170") (name "unconnected-(J1-Pad207)") (class "Default")
      (node (ref "J1") (pin "207") (pinfunction "207_207") (pintype "passive+no_connect"))
    )
    (net (code "171") (name "unconnected-(J1-Pad209)") (class "Default")
      (node (ref "J1") (pin "209") (pinfunction "209_209") (pintype "passive+no_connect"))
    )
    (net (code "172") (name "unconnected-(J1-Pad212)") (class "Default")
      (node (ref "J1") (pin "212") (pinfunction "212_212") (pintype "passive+no_connect"))
    )
    (net (code "173") (name "unconnected-(J1-Pad216)") (class "Default")
      (node (ref "J1") (pin "216") (pinfunction "216_216") (pintype "passive+no_connect"))
    )
    (net (code "174") (name "unconnected-(J1-Pad217)") (class "Default")
      (node (ref "J1") (pin "217") (pinfunction "217_217") (pintype "passive+no_connect"))
    )
    (net (code "175") (name "unconnected-(J1-Pad218)") (class "Default")
      (node (ref "J1") (pin "218") (pinfunction "218_218") (pintype "passive+no_connect"))
    )
    (net (code "176") (name "unconnected-(J1-Pad219)") (class "Default")
      (node (ref "J1") (pin "219") (pinfunction "219_219") (pintype "passive+no_connect"))
    )
    (net (code "177") (name "unconnected-(J1-Pad220)") (class "Default")
      (node (ref "J1") (pin "220") (pinfunction "220_220") (pintype "passive+no_connect"))
    )
    (net (code "178") (name "unconnected-(J1-Pad221)") (class "Default")
      (node (ref "J1") (pin "221") (pinfunction "221_221") (pintype "passive+no_connect"))
    )
    (net (code "179") (name "unconnected-(J1-Pad222)") (class "Default")
      (node (ref "J1") (pin "222") (pinfunction "222_222") (pintype "passive+no_connect"))
    )
    (net (code "180") (name "unconnected-(J1-Pad223)") (class "Default")
      (node (ref "J1") (pin "223") (pinfunction "223_223") (pintype "passive+no_connect"))
    )
    (net (code "181") (name "unconnected-(J1-Pad224)") (class "Default")
      (node (ref "J1") (pin "224") (pinfunction "224_224") (pintype "passive+no_connect"))
    )
    (net (code "182") (name "unconnected-(J1-Pad225)") (class "Default")
      (node (ref "J1") (pin "225") (pinfunction "225_225") (pintype "passive+no_connect"))
    )
    (net (code "183") (name "unconnected-(J1-Pad226)") (class "Default")
      (node (ref "J1") (pin "226") (pinfunction "226_226") (pintype "passive+no_connect"))
    )
    (net (code "184") (name "unconnected-(J1-Pad227)") (class "Default")
      (node (ref "J1") (pin "227") (pinfunction "227_227") (pintype "passive+no_connect"))
    )
    (net (code "185") (name "unconnected-(J1-Pad228)") (class "Default")
      (node (ref "J1") (pin "228") (pinfunction "228_228") (pintype "passive+no_connect"))
    )
    (net (code "186") (name "unconnected-(J1-Pad229)") (class "Default")
      (node (ref "J1") (pin "229") (pinfunction "229_229") (pintype "passive+no_connect"))
    )
    (net (code "187") (name "unconnected-(J1-Pad232)") (class "Default")
      (node (ref "J1") (pin "232") (pinfunction "232_232") (pintype "passive+no_connect"))
    )
    (net (code "188") (name "unconnected-(J1-Pad234)") (class "Default")
      (node (ref "J1") (pin "234") (pinfunction "234_234") (pintype "passive+no_connect"))
    )
    (net (code "189") (name "unconnected-(J1-Pad235)") (class "Default")
      (node (ref "J1") (pin "235") (pinfunction "235_235") (pintype "passive+no_connect"))
    )
    (net (code "190") (name "unconnected-(J1-Pad236)") (class "Default")
      (node (ref "J1") (pin "236") (pinfunction "236_236") (pintype "passive+no_connect"))
    )
    (net (code "191") (name "unconnected-(J1-Pad238)") (class "Default")
      (node (ref "J1") (pin "238") (pinfunction "238_238") (pintype "passive+no_connect"))
    )
    (net (code "192") (name "unconnected-(J1-Pad240)") (class "Default")
      (node (ref "J1") (pin "240") (pinfunction "240_240") (pintype "passive+no_connect"))
    )
  )
)
